# M_2_SoM_breakout_board_v0_5.net
KiCad netlist of a schematic drawn in EAGLE
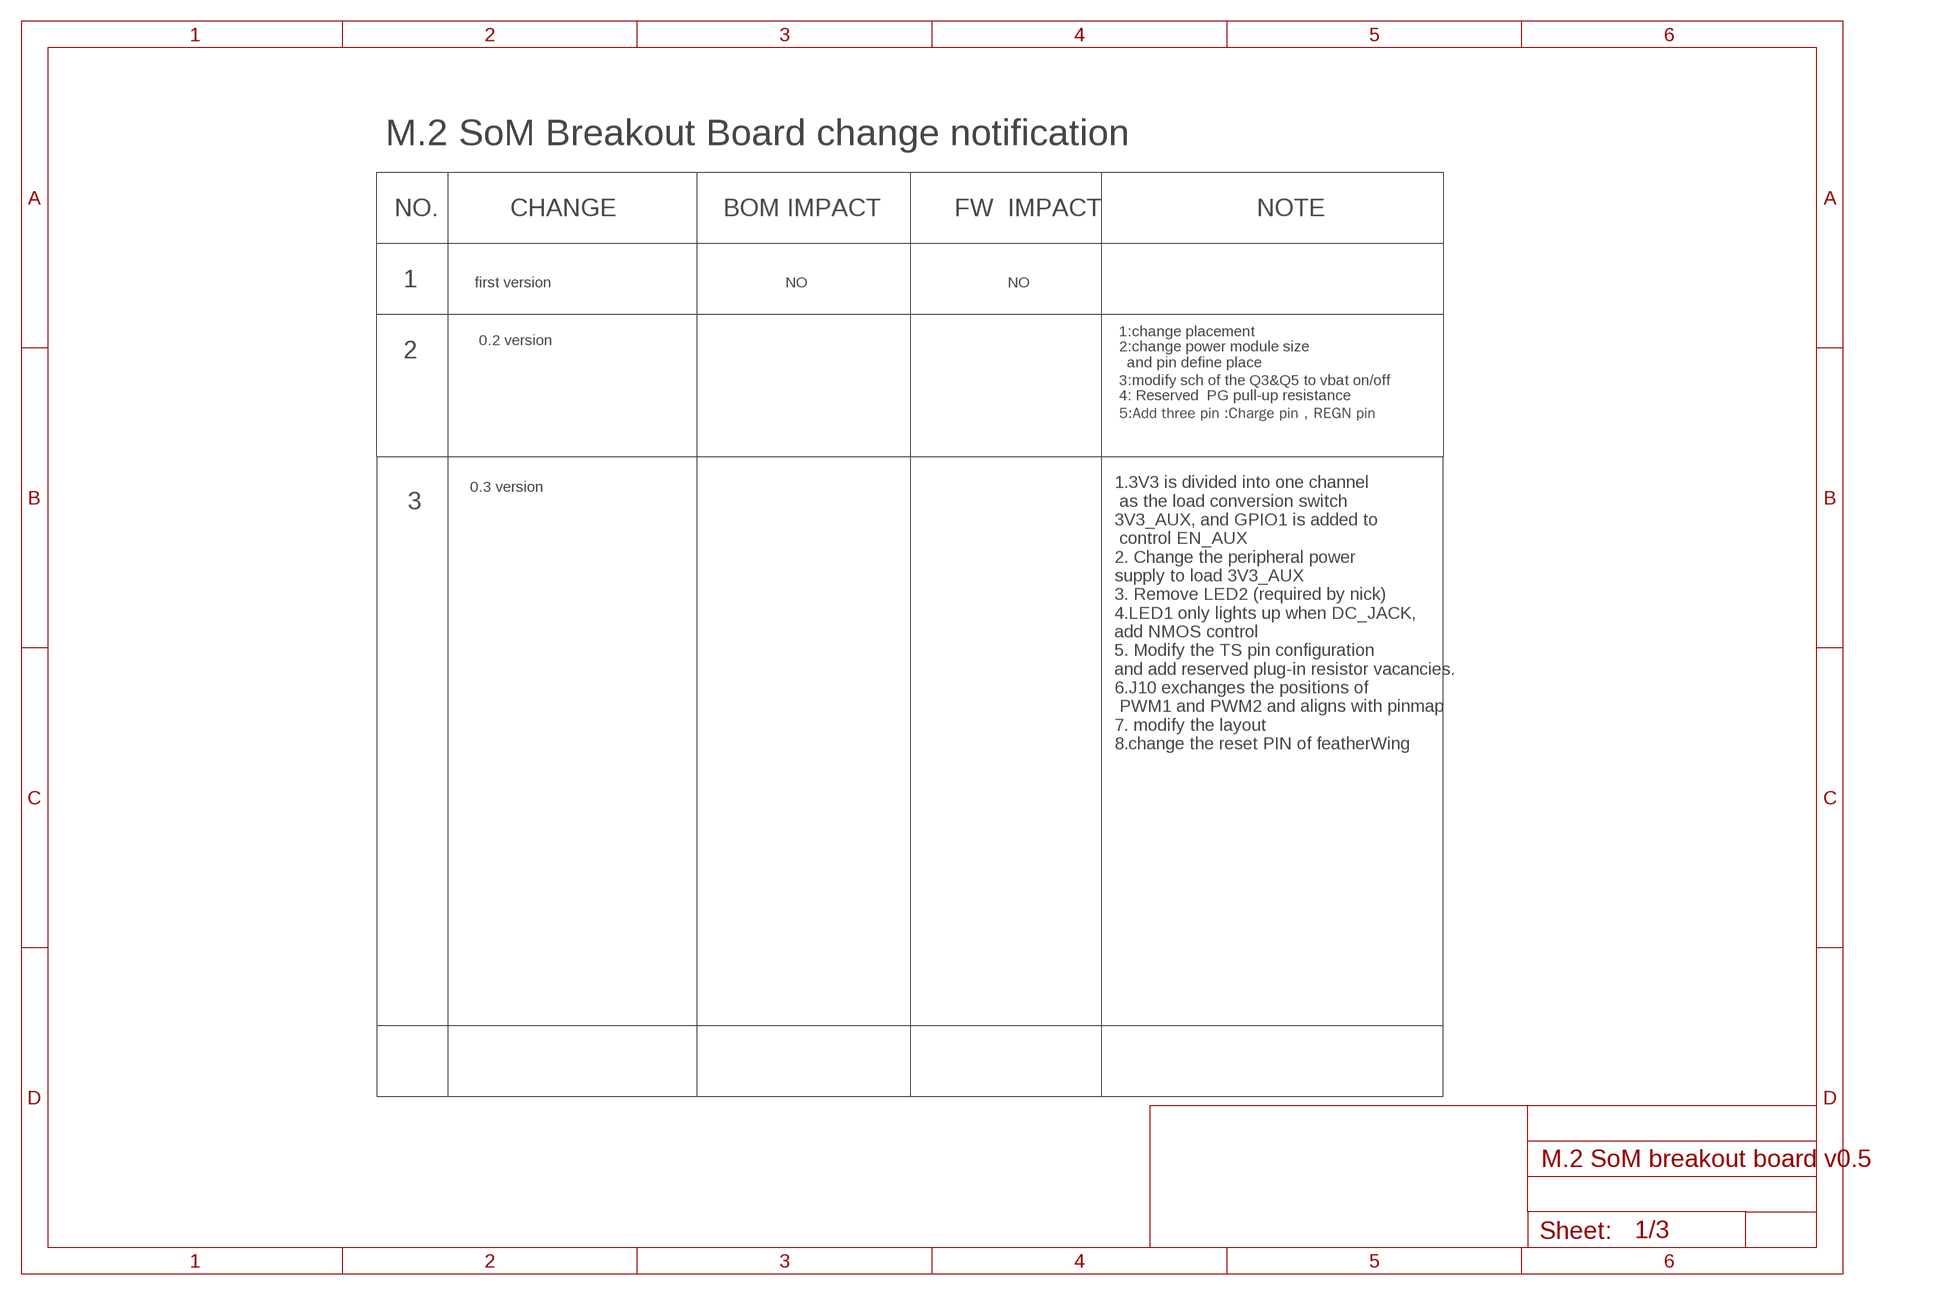
[diagram p0: schematic, sheet 1]
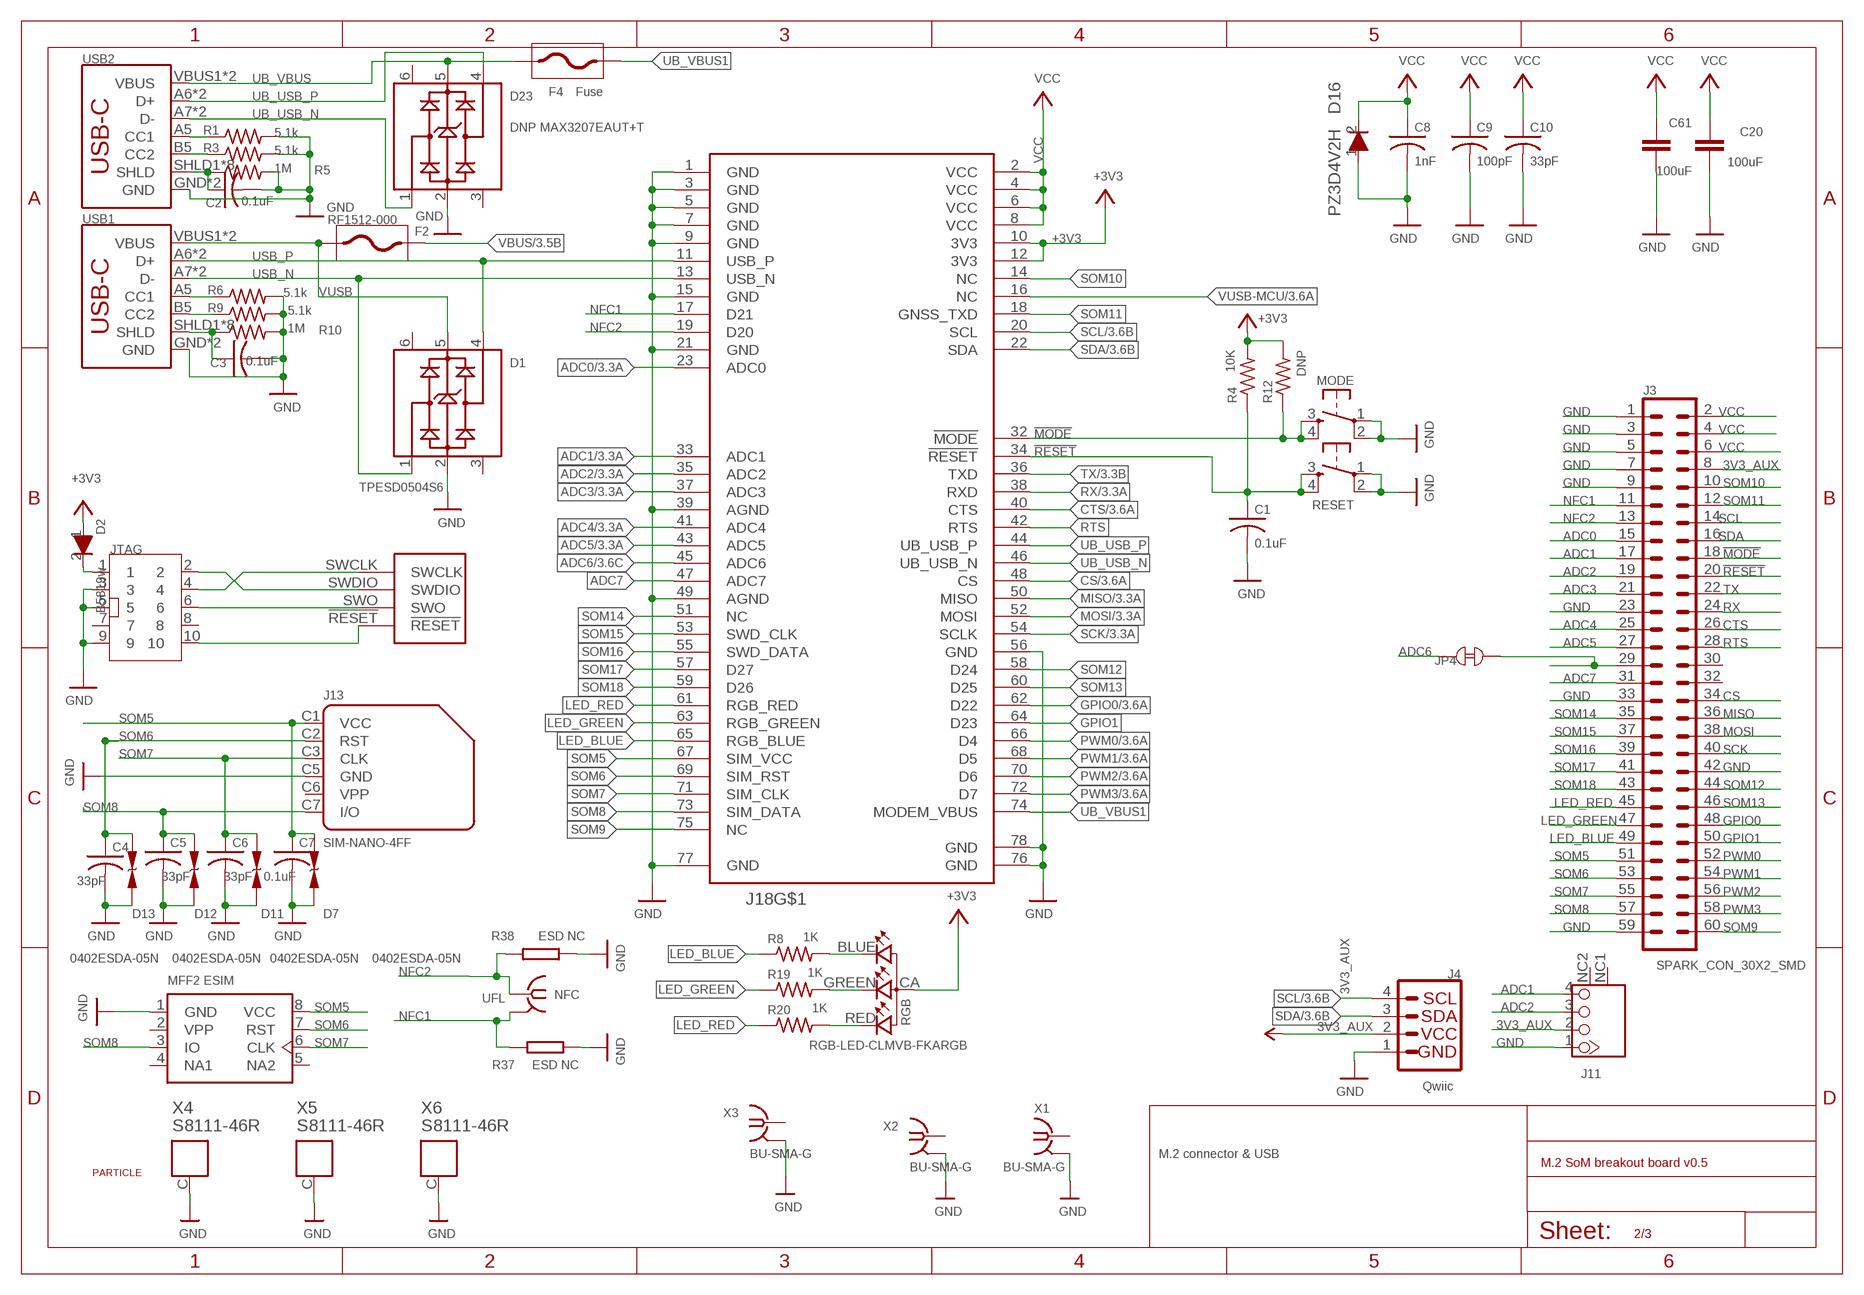
[diagram p1: schematic, sheet 2]
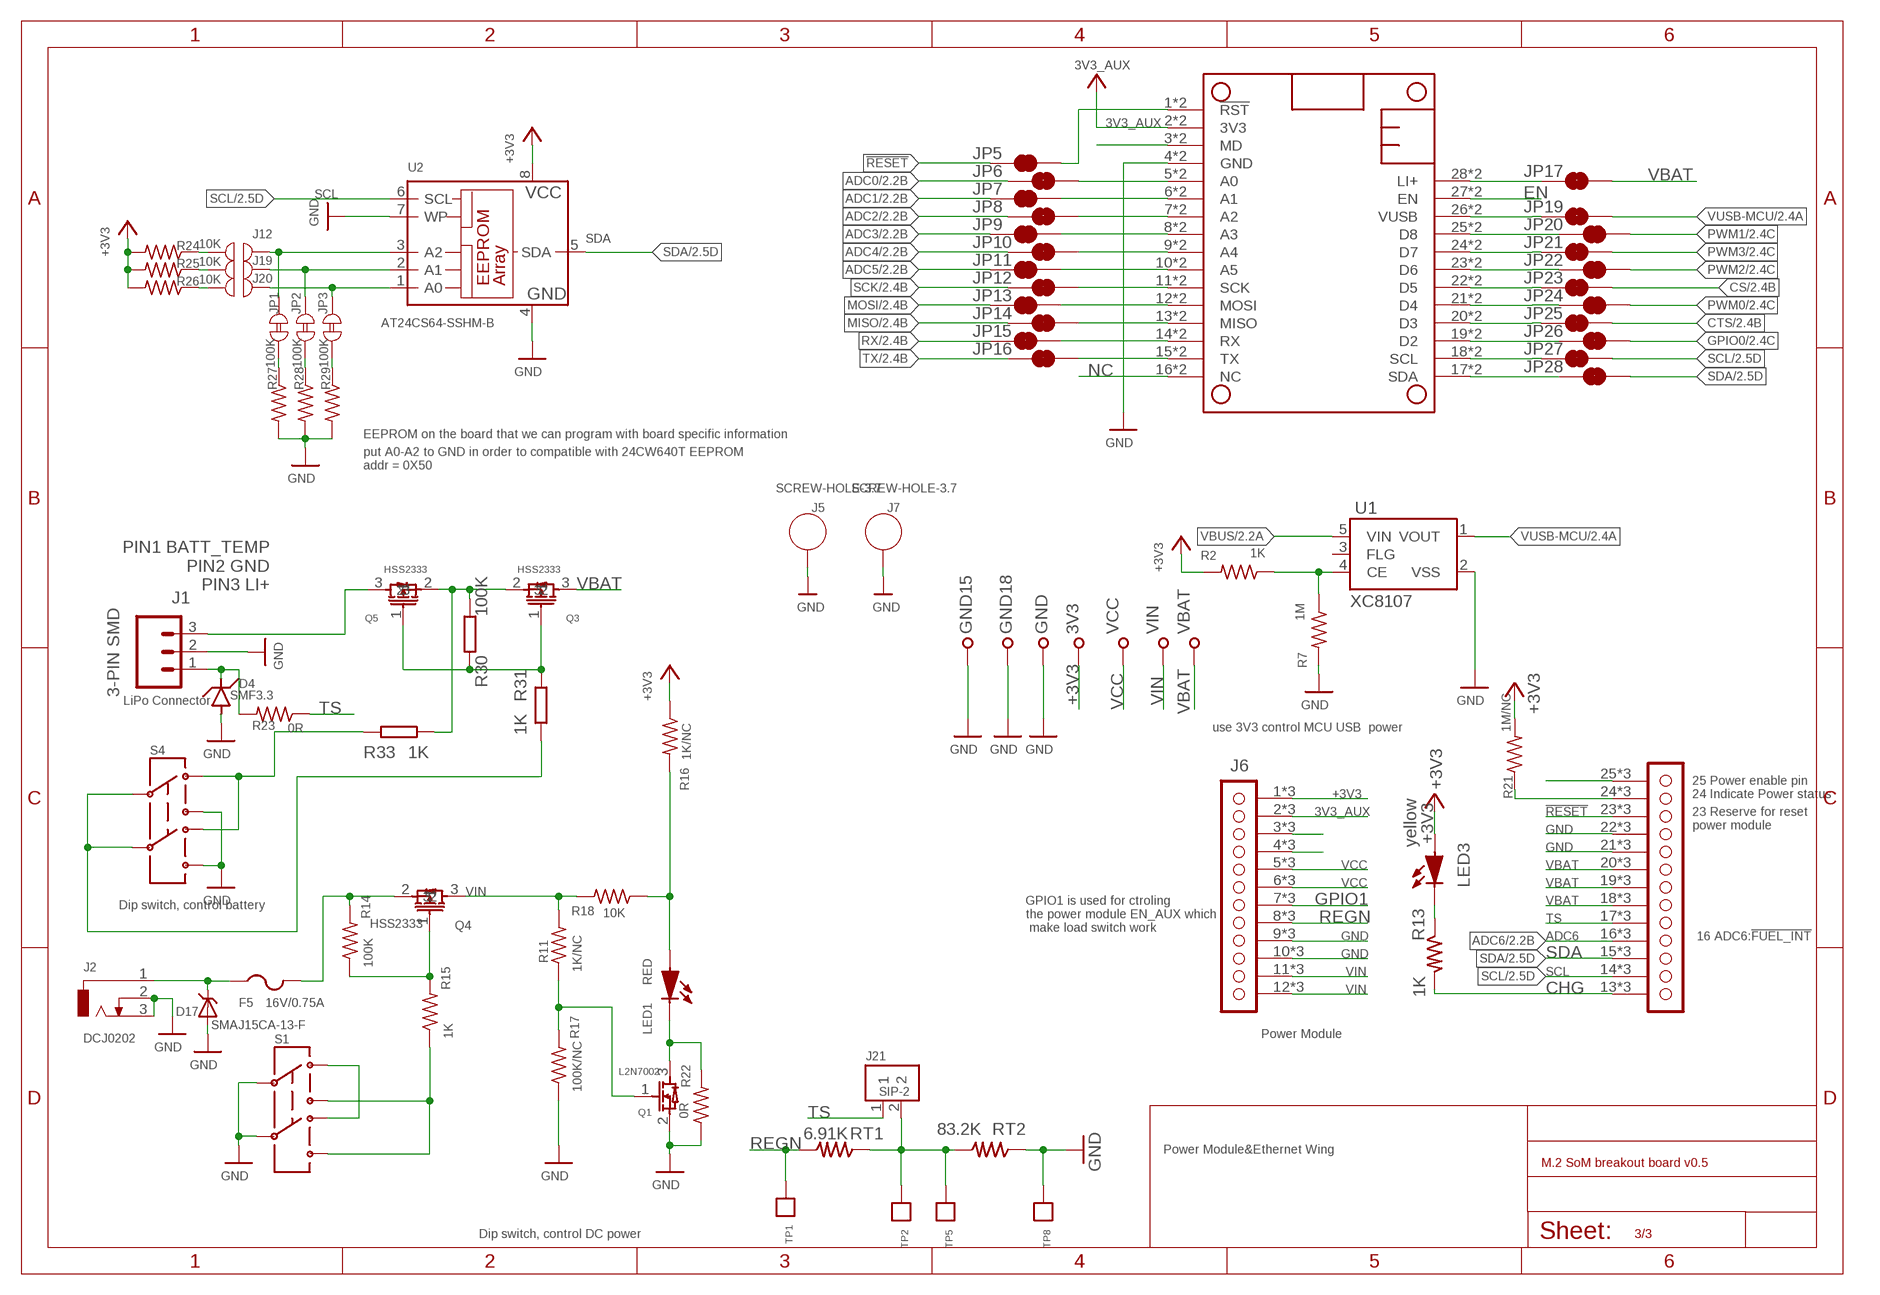
[diagram p2: schematic, sheet 3]

(export (version "E")
  (design (tool "Eeschema 10.0.6"))
  (components
    (comp (ref "3V3")
      (value "TP-S2751-46R")
      (footprint "eagle-import:S2751-46R")
      (libsource (lib "eagle-import") (part "TP-S2751-46R"))
    )
    (comp (ref "D4")
      (value "SMF3.3")
      (footprint "eagle-import:SOD-123FL")
      (libsource (lib "eagle-import") (part "TVS-DIODE-SOD123FL"))
    )
    (comp (ref "D17")
      (value "SMAJ15CA-13-F")
      (footprint "eagle-import:SMADIODE")
      (libsource (lib "eagle-import") (part "DIODE-ZENER"))
    )
    (comp (ref "F5")
      (value "16V/0.75A")
      (footprint "eagle-import:1812")
      (libsource (lib "eagle-import") (part "PTCFUSE-1812"))
    )
    (comp (ref "GND")
      (value "TP-S2751-46R")
      (footprint "eagle-import:S2751-46R")
      (libsource (lib "eagle-import") (part "TP-S2751-46R"))
    )
    (comp (ref "GND15")
      (value "TP-S2751-46R")
      (footprint "eagle-import:S2751-46R")
      (libsource (lib "eagle-import") (part "TP-S2751-46R"))
    )
    (comp (ref "GND18")
      (value "TP-S2751-46R")
      (footprint "eagle-import:S2751-46R")
      (libsource (lib "eagle-import") (part "TP-S2751-46R"))
    )
    (comp (ref "J1")
      (value "3-PIN SMD")
      (footprint "eagle-import:JST-3-SMD")
      (libsource (lib "eagle-import") (part "CONN_03JST-SMD"))
    )
    (comp (ref "J2")
      (value "DCJ0202")
      (footprint "eagle-import:DCJ0202")
      (libsource (lib "eagle-import") (part "DCJ0202"))
    )
    (comp (ref "J5")
      (value "SCREW-HOLE-3.7")
      (footprint "eagle-import:SCREW-HOLE-3.7")
      (libsource (lib "eagle-import") (part "SCREW-HOLE-3.7"))
    )
    (comp (ref "J6")
      (value "M.2-SOM-BREAKOUT-BOARD-V0.2-0228_PARTICLE-SZ_PARTICLE-POWER-MODULE")
      (footprint "eagle-import:M.2-SOM-BREAKOUT-BOARD-V0.2-0228_PARTICLE-SZ_PARTICLE-POWER-MODULE")
      (libsource (lib "eagle-import") (part "M.2-SOM-BREAKOUT-BOARD-V0.2-0228_PARTICLE-SZ_PARTICLE-POWER-MODULE"))
    )
    (comp (ref "J7")
      (value "SCREW-HOLE-3.7")
      (footprint "eagle-import:SCREW-HOLE-3.7")
      (libsource (lib "eagle-import") (part "SCREW-HOLE-3.7"))
    )
    (comp (ref "J12")
      (value "TP_OPEN")
      (footprint "eagle-import:TP_OPEN")
      (libsource (lib "eagle-import") (part "TP_OPEN"))
    )
    (comp (ref "J19")
      (value "TP_OPEN")
      (footprint "eagle-import:TP_OPEN")
      (libsource (lib "eagle-import") (part "TP_OPEN"))
    )
    (comp (ref "J20")
      (value "TP_OPEN")
      (footprint "eagle-import:TP_OPEN")
      (libsource (lib "eagle-import") (part "TP_OPEN"))
    )
    (comp (ref "J21")
      (value "SIP-2")
      (footprint "eagle-import:SIP-2")
      (libsource (lib "eagle-import") (part "SIP-2"))
    )
    (comp (ref "JP1")
      (value "TP_SHORT")
      (footprint "eagle-import:TP_SHORT")
      (libsource (lib "eagle-import") (part "TP_SHORT"))
    )
    (comp (ref "JP2")
      (value "TP_SHORT")
      (footprint "eagle-import:TP_SHORT")
      (libsource (lib "eagle-import") (part "TP_SHORT"))
    )
    (comp (ref "JP3")
      (value "TP_SHORT")
      (footprint "eagle-import:TP_SHORT")
      (libsource (lib "eagle-import") (part "TP_SHORT"))
    )
    (comp (ref "JP5")
      (value "JUMPER-SMT_2_NC_TRACE_NO-SILK")
      (footprint "eagle-import:SMT-JUMPER_2_NC_TRACE_NO-SILK")
      (libsource (lib "eagle-import") (part "JUMPER-SMT_2_NC_TRACE_NO-SILK"))
    )
    (comp (ref "JP6")
      (value "JUMPER-SMT_2_NC_TRACE_NO-SILK")
      (footprint "eagle-import:SMT-JUMPER_2_NC_TRACE_NO-SILK")
      (libsource (lib "eagle-import") (part "JUMPER-SMT_2_NC_TRACE_NO-SILK"))
    )
    (comp (ref "JP7")
      (value "JUMPER-SMT_2_NC_TRACE_NO-SILK")
      (footprint "eagle-import:SMT-JUMPER_2_NC_TRACE_NO-SILK")
      (libsource (lib "eagle-import") (part "JUMPER-SMT_2_NC_TRACE_NO-SILK"))
    )
    (comp (ref "JP8")
      (value "JUMPER-SMT_2_NC_TRACE_NO-SILK")
      (footprint "eagle-import:SMT-JUMPER_2_NC_TRACE_NO-SILK")
      (libsource (lib "eagle-import") (part "JUMPER-SMT_2_NC_TRACE_NO-SILK"))
    )
    (comp (ref "JP9")
      (value "JUMPER-SMT_2_NC_TRACE_NO-SILK")
      (footprint "eagle-import:SMT-JUMPER_2_NC_TRACE_NO-SILK")
      (libsource (lib "eagle-import") (part "JUMPER-SMT_2_NC_TRACE_NO-SILK"))
    )
    (comp (ref "JP10")
      (value "JUMPER-SMT_2_NC_TRACE_NO-SILK")
      (footprint "eagle-import:SMT-JUMPER_2_NC_TRACE_NO-SILK")
      (libsource (lib "eagle-import") (part "JUMPER-SMT_2_NC_TRACE_NO-SILK"))
    )
    (comp (ref "JP11")
      (value "JUMPER-SMT_2_NC_TRACE_NO-SILK")
      (footprint "eagle-import:SMT-JUMPER_2_NC_TRACE_NO-SILK")
      (libsource (lib "eagle-import") (part "JUMPER-SMT_2_NC_TRACE_NO-SILK"))
    )
    (comp (ref "JP12")
      (value "JUMPER-SMT_2_NC_TRACE_NO-SILK")
      (footprint "eagle-import:SMT-JUMPER_2_NC_TRACE_NO-SILK")
      (libsource (lib "eagle-import") (part "JUMPER-SMT_2_NC_TRACE_NO-SILK"))
    )
    (comp (ref "JP13")
      (value "JUMPER-SMT_2_NC_TRACE_NO-SILK")
      (footprint "eagle-import:SMT-JUMPER_2_NC_TRACE_NO-SILK")
      (libsource (lib "eagle-import") (part "JUMPER-SMT_2_NC_TRACE_NO-SILK"))
    )
    (comp (ref "JP14")
      (value "JUMPER-SMT_2_NC_TRACE_NO-SILK")
      (footprint "eagle-import:SMT-JUMPER_2_NC_TRACE_NO-SILK")
      (libsource (lib "eagle-import") (part "JUMPER-SMT_2_NC_TRACE_NO-SILK"))
    )
    (comp (ref "JP15")
      (value "JUMPER-SMT_2_NC_TRACE_NO-SILK")
      (footprint "eagle-import:SMT-JUMPER_2_NC_TRACE_NO-SILK")
      (libsource (lib "eagle-import") (part "JUMPER-SMT_2_NC_TRACE_NO-SILK"))
    )
    (comp (ref "JP16")
      (value "JUMPER-SMT_2_NC_TRACE_NO-SILK")
      (footprint "eagle-import:SMT-JUMPER_2_NC_TRACE_NO-SILK")
      (libsource (lib "eagle-import") (part "JUMPER-SMT_2_NC_TRACE_NO-SILK"))
    )
    (comp (ref "JP17")
      (value "JUMPER-SMT_2_NC_TRACE_NO-SILK")
      (footprint "eagle-import:SMT-JUMPER_2_NC_TRACE_NO-SILK")
      (libsource (lib "eagle-import") (part "JUMPER-SMT_2_NC_TRACE_NO-SILK"))
    )
    (comp (ref "JP19")
      (value "JUMPER-SMT_2_NC_TRACE_NO-SILK")
      (footprint "eagle-import:SMT-JUMPER_2_NC_TRACE_NO-SILK")
      (libsource (lib "eagle-import") (part "JUMPER-SMT_2_NC_TRACE_NO-SILK"))
    )
    (comp (ref "JP20")
      (value "JUMPER-SMT_2_NC_TRACE_NO-SILK")
      (footprint "eagle-import:SMT-JUMPER_2_NC_TRACE_NO-SILK")
      (libsource (lib "eagle-import") (part "JUMPER-SMT_2_NC_TRACE_NO-SILK"))
    )
    (comp (ref "JP21")
      (value "JUMPER-SMT_2_NC_TRACE_NO-SILK")
      (footprint "eagle-import:SMT-JUMPER_2_NC_TRACE_NO-SILK")
      (libsource (lib "eagle-import") (part "JUMPER-SMT_2_NC_TRACE_NO-SILK"))
    )
    (comp (ref "JP22")
      (value "JUMPER-SMT_2_NC_TRACE_NO-SILK")
      (footprint "eagle-import:SMT-JUMPER_2_NC_TRACE_NO-SILK")
      (libsource (lib "eagle-import") (part "JUMPER-SMT_2_NC_TRACE_NO-SILK"))
    )
    (comp (ref "JP23")
      (value "JUMPER-SMT_2_NC_TRACE_NO-SILK")
      (footprint "eagle-import:SMT-JUMPER_2_NC_TRACE_NO-SILK")
      (libsource (lib "eagle-import") (part "JUMPER-SMT_2_NC_TRACE_NO-SILK"))
    )
    (comp (ref "JP24")
      (value "JUMPER-SMT_2_NC_TRACE_NO-SILK")
      (footprint "eagle-import:SMT-JUMPER_2_NC_TRACE_NO-SILK")
      (libsource (lib "eagle-import") (part "JUMPER-SMT_2_NC_TRACE_NO-SILK"))
    )
    (comp (ref "JP25")
      (value "JUMPER-SMT_2_NC_TRACE_NO-SILK")
      (footprint "eagle-import:SMT-JUMPER_2_NC_TRACE_NO-SILK")
      (libsource (lib "eagle-import") (part "JUMPER-SMT_2_NC_TRACE_NO-SILK"))
    )
    (comp (ref "JP26")
      (value "JUMPER-SMT_2_NC_TRACE_NO-SILK")
      (footprint "eagle-import:SMT-JUMPER_2_NC_TRACE_NO-SILK")
      (libsource (lib "eagle-import") (part "JUMPER-SMT_2_NC_TRACE_NO-SILK"))
    )
    (comp (ref "JP27")
      (value "JUMPER-SMT_2_NC_TRACE_NO-SILK")
      (footprint "eagle-import:SMT-JUMPER_2_NC_TRACE_NO-SILK")
      (libsource (lib "eagle-import") (part "JUMPER-SMT_2_NC_TRACE_NO-SILK"))
    )
    (comp (ref "JP28")
      (value "JUMPER-SMT_2_NC_TRACE_NO-SILK")
      (footprint "eagle-import:SMT-JUMPER_2_NC_TRACE_NO-SILK")
      (libsource (lib "eagle-import") (part "JUMPER-SMT_2_NC_TRACE_NO-SILK"))
    )
    (comp (ref "LED1")
      (value "RED")
      (footprint "eagle-import:LED0603")
      (libsource (lib "eagle-import") (part "LED"))
    )
    (comp (ref "LED3")
      (value "yellow")
      (footprint "eagle-import:LED0603")
      (libsource (lib "eagle-import") (part "LED"))
    )
    (comp (ref "MS1")
      (value "PARTICLE_MESH_SMTDUAL")
      (footprint "eagle-import:FEATHERWING_SMT2")
      (libsource (lib "eagle-import") (part "PARTICLE_MESH_SMTDUAL"))
    )
    (comp (ref "Q1")
      (value "L2N7002")
      (footprint "eagle-import:SOT323")
      (libsource (lib "eagle-import") (part "NMOSSOT323"))
    )
    (comp (ref "Q3")
      (value "HSS2333")
      (footprint "eagle-import:SOT-23")
      (libsource (lib "eagle-import") (part "PMOS"))
    )
    (comp (ref "Q4")
      (value "HSS2333")
      (footprint "eagle-import:SOT-23")
      (libsource (lib "eagle-import") (part "PMOS"))
    )
    (comp (ref "Q5")
      (value "HSS2333")
      (footprint "eagle-import:SOT-23")
      (libsource (lib "eagle-import") (part "PMOS"))
    )
    (comp (ref "R2")
      (value "1K")
      (footprint "eagle-import:R0402_B")
      (libsource (lib "eagle-import") (part "R-US_"))
    )
    (comp (ref "R7")
      (value "1M")
      (footprint "eagle-import:R0402_B")
      (libsource (lib "eagle-import") (part "R-US_"))
    )
    (comp (ref "R11")
      (value "1K/NC")
      (footprint "eagle-import:R0402_B")
      (libsource (lib "eagle-import") (part "R-US_"))
    )
    (comp (ref "R13")
      (value "1K")
      (footprint "eagle-import:R-0402S")
      (libsource (lib "eagle-import") (part "particle SZ_RES0402S"))
    )
    (comp (ref "R14")
      (value "100K")
      (footprint "eagle-import:R0402_B")
      (libsource (lib "eagle-import") (part "R-US_"))
    )
    (comp (ref "R15")
      (value "1K")
      (footprint "eagle-import:R0402_B")
      (libsource (lib "eagle-import") (part "R-US_"))
    )
    (comp (ref "R16")
      (value "1K/NC")
      (footprint "eagle-import:R0402_B")
      (libsource (lib "eagle-import") (part "R-US_"))
    )
    (comp (ref "R17")
      (value "100K/NC")
      (footprint "eagle-import:R0402_B")
      (libsource (lib "eagle-import") (part "R-US_"))
    )
    (comp (ref "R18")
      (value "10K")
      (footprint "eagle-import:R0402_B")
      (libsource (lib "eagle-import") (part "R-US_"))
    )
    (comp (ref "R21")
      (value "1M/NC")
      (footprint "eagle-import:R0402_B")
      (libsource (lib "eagle-import") (part "R-US_"))
    )
    (comp (ref "R22")
      (value "0R")
      (footprint "eagle-import:R0402_B")
      (libsource (lib "eagle-import") (part "R-US_"))
    )
    (comp (ref "R23")
      (value "0R")
      (footprint "eagle-import:R0402_B")
      (libsource (lib "eagle-import") (part "R-US_"))
    )
    (comp (ref "R24")
      (value "10K")
      (footprint "eagle-import:R0402_B")
      (libsource (lib "eagle-import") (part "R-US_"))
    )
    (comp (ref "R25")
      (value "10K")
      (footprint "eagle-import:R0402_B")
      (libsource (lib "eagle-import") (part "R-US_"))
    )
    (comp (ref "R26")
      (value "10K")
      (footprint "eagle-import:R0402_B")
      (libsource (lib "eagle-import") (part "R-US_"))
    )
    (comp (ref "R27")
      (value "100K")
      (footprint "eagle-import:R0402_B")
      (libsource (lib "eagle-import") (part "R-US_"))
    )
    (comp (ref "R28")
      (value "100K")
      (footprint "eagle-import:R0402_B")
      (libsource (lib "eagle-import") (part "R-US_"))
    )
    (comp (ref "R29")
      (value "100K")
      (footprint "eagle-import:R0402_B")
      (libsource (lib "eagle-import") (part "R-US_"))
    )
    (comp (ref "R30")
      (value "100K")
      (footprint "eagle-import:R0603")
      (libsource (lib "eagle-import") (part "RESR0603"))
    )
    (comp (ref "R31")
      (value "1K")
      (footprint "eagle-import:R-0402S")
      (libsource (lib "eagle-import") (part "RES0402S"))
    )
    (comp (ref "R33")
      (value "1K")
      (footprint "eagle-import:R-0402S")
      (libsource (lib "eagle-import") (part "RES0402S"))
    )
    (comp (ref "RT1")
      (value "6.91K")
      (footprint "eagle-import:R-0603A")
      (libsource (lib "eagle-import") (part "RESR0603A"))
    )
    (comp (ref "RT2")
      (value "83.2K")
      (footprint "eagle-import:R-0603A")
      (libsource (lib "eagle-import") (part "RESR0603A"))
    )
    (comp (ref "S1")
      (value "SWITCH-DPDT")
      (footprint "eagle-import:SWITCH-2.5X3.2-6")
      (libsource (lib "eagle-import") (part "SWITCH-DPDT"))
    )
    (comp (ref "S4")
      (value "SWITCH-DPDT")
      (footprint "eagle-import:SWITCH-2.5X3.2-6")
      (libsource (lib "eagle-import") (part "SWITCH-DPDT"))
    )
    (comp (ref "TP1")
      (value "TPTPEB")
      (footprint "eagle-import:TPEB")
      (libsource (lib "eagle-import") (part "TPTPEB"))
    )
    (comp (ref "TP2")
      (value "TPTPEB")
      (footprint "eagle-import:TPEB")
      (libsource (lib "eagle-import") (part "TPTPEB"))
    )
    (comp (ref "TP5")
      (value "TPTPEB")
      (footprint "eagle-import:TPEB")
      (libsource (lib "eagle-import") (part "TPTPEB"))
    )
    (comp (ref "TP8")
      (value "TPTPEB")
      (footprint "eagle-import:TPEB")
      (libsource (lib "eagle-import") (part "TPTPEB"))
    )
    (comp (ref "U1")
      (value "XC8107")
      (footprint "eagle-import:SOT25")
      (libsource (lib "eagle-import") (part "XC8107SOT25"))
    )
    (comp (ref "U2")
      (value "AT24CS64-SSHM-B")
      (footprint "eagle-import:SO-08")
      (fields (field (name "MF") "MICROCHIP") (field (name "MPN") "24AA01/SN"))
      (libsource (lib "eagle-import") (part "24SNAA01"))
    )
    (comp (ref "VBAT")
      (value "TP-S2751-46R")
      (footprint "eagle-import:S2751-46R")
      (libsource (lib "eagle-import") (part "TP-S2751-46R"))
    )
    (comp (ref "VCC")
      (value "TP-S2751-46R")
      (footprint "eagle-import:S2751-46R")
      (libsource (lib "eagle-import") (part "TP-S2751-46R"))
    )
    (comp (ref "VIN")
      (value "TP-S2751-46R")
      (footprint "eagle-import:S2751-46R")
      (libsource (lib "eagle-import") (part "TP-S2751-46R"))
    )
    (comp (ref "C1")
      (value "0.1uF")
      (footprint "eagle-import:C0402_B")
      (libsource (lib "eagle-import") (part "C-US"))
    )
    (comp (ref "C2")
      (value "0.1uF")
      (footprint "eagle-import:C0402_B")
      (libsource (lib "eagle-import") (part "C-US"))
    )
    (comp (ref "C3")
      (value "0.1uF")
      (footprint "eagle-import:C0402_B")
      (libsource (lib "eagle-import") (part "C-US"))
    )
    (comp (ref "C4")
      (value "33pF")
      (footprint "eagle-import:C0402_B")
      (libsource (lib "eagle-import") (part "C-US"))
    )
    (comp (ref "C5")
      (value "33pF")
      (footprint "eagle-import:C0402_B")
      (libsource (lib "eagle-import") (part "C-US"))
    )
    (comp (ref "C6")
      (value "33pF")
      (footprint "eagle-import:C0402_B")
      (libsource (lib "eagle-import") (part "C-US"))
    )
    (comp (ref "C7")
      (value "0.1uF")
      (footprint "eagle-import:C0402_B")
      (libsource (lib "eagle-import") (part "C-US"))
    )
    (comp (ref "C8")
      (value "1nF")
      (footprint "eagle-import:C0402_B")
      (libsource (lib "eagle-import") (part "C-US"))
    )
    (comp (ref "C9")
      (value "100pF")
      (footprint "eagle-import:C0402_B")
      (libsource (lib "eagle-import") (part "C-US"))
    )
    (comp (ref "C10")
      (value "33pF")
      (footprint "eagle-import:C0402_B")
      (libsource (lib "eagle-import") (part "C-US"))
    )
    (comp (ref "C20")
      (value "100uF")
      (footprint "eagle-import:C1206K")
      (libsource (lib "eagle-import") (part "C-EUC1206K"))
    )
    (comp (ref "C61")
      (value "100uF")
      (footprint "eagle-import:C1206K")
      (libsource (lib "eagle-import") (part "C-EUC1206K"))
    )
    (comp (ref "D1")
      (value "TPESD0504S6")
      (footprint "eagle-import:SOT23-6")
      (fields (field (name "MFG") "MAXIM") (field (name "MPN") "MAX3207EAUT+T"))
      (libsource (lib "eagle-import") (part "MAX3207EAUT+T"))
    )
    (comp (ref "D2")
      (value "B5819w")
      (footprint "eagle-import:SOD-123")
      (libsource (lib "eagle-import") (part "DIODESOD123"))
    )
    (comp (ref "D7")
      (value "0402ESDA-05N")
      (footprint "eagle-import:C0402")
      (libsource (lib "eagle-import") (part "ESD"))
    )
    (comp (ref "D11")
      (value "0402ESDA-05N")
      (footprint "eagle-import:C0402")
      (libsource (lib "eagle-import") (part "ESD"))
    )
    (comp (ref "D12")
      (value "0402ESDA-05N")
      (footprint "eagle-import:C0402")
      (libsource (lib "eagle-import") (part "ESD"))
    )
    (comp (ref "D13")
      (value "0402ESDA-05N")
      (footprint "eagle-import:C0402")
      (libsource (lib "eagle-import") (part "ESD"))
    )
    (comp (ref "D16")
      (value "PZ3D4V2H")
      (footprint "eagle-import:SOD-323")
      (libsource (lib "eagle-import") (part "DIODESOD323"))
    )
    (comp (ref "D23")
      (value "DNP MAX3207EAUT+T")
      (footprint "eagle-import:SOT23-6")
      (fields (field (name "MFG") "MAXIM") (field (name "MPN") "MAX3207EAUT+T"))
      (libsource (lib "eagle-import") (part "MAX3207EAUT+T"))
    )
    (comp (ref "F2")
      (value "RF1512-000")
      (footprint "eagle-import:F0805")
      (libsource (lib "eagle-import") (part "FUSE"))
    )
    (comp (ref "F4")
      (value "Fuse")
      (footprint "eagle-import:F0805")
      (libsource (lib "eagle-import") (part "FUSE"))
    )
    (comp (ref "J3")
      (value "SPARK_CON_30X2_SMD")
      (footprint "eagle-import:SPARK_CON_30X2_SMD")
      (libsource (lib "eagle-import") (part "SPARK_CON_30X2_SMD"))
    )
    (comp (ref "J4")
      (value "QWIIC_CONNECTORJS-1MM")
      (footprint "eagle-import:1X04_1MM_RA")
      (libsource (lib "eagle-import") (part "QWIIC_CONNECTORJS-1MM"))
    )
    (comp (ref "J11")
      (value "WAFER-HY2.0-4PWB")
      (footprint "eagle-import:M.2-SOM-BREAKOUT-BOARD-V0.2-0228_WAFER-HY2.0-4PWB")
      (libsource (lib "eagle-import") (part "M.2-SOM-BREAKOUT-BOARD-V0.2-0228_WAFER-HY2.0-4PWB"))
    )
    (comp (ref "J13")
      (value "SIM-NANO-4FF")
      (footprint "eagle-import:GCT-SIM8100")
      (libsource (lib "eagle-import") (part "SIM-NANO-4FF"))
    )
    (comp (ref "J18")
      (value "PARTICLE-STUDIOS_M_SERIES_M.2KEY")
      (footprint "eagle-import:PARTICLE-STUDIOS_PARTICLE_M.2EKEY_3.65MM_DRILL")
      (libsource (lib "eagle-import") (part "PARTICLE-STUDIOS_M_SERIES_M.2KEY"))
    )
    (comp (ref "JP4")
      (value "TP_SHORT")
      (footprint "eagle-import:TP_SHORT")
      (libsource (lib "eagle-import") (part "TP_SHORT"))
    )
    (comp (ref "JTAG")
      (value "CONN5X2")
      (footprint "eagle-import:CONN5X2_1.27")
      (fields (field (name "MFG") "KAWEEI") (field (name "MPN") "P6014A-M2GC-030-10"))
      (libsource (lib "eagle-import") (part "CONN5X2"))
    )
    (comp (ref "MODE")
      (value "TAC_SWITCHSMD")
      (footprint "eagle-import:TACTILE_SWITCH_SMD")
      (fields (field (name "MFG") "HAOYU") (field (name "MPN") "TS-1185A-025C"))
      (libsource (lib "eagle-import") (part "TAC_SWITCHSMD"))
    )
    (comp (ref "NFC")
      (value "UFL")
      (footprint "eagle-import:IPEX-20279-001E")
      (libsource (lib "eagle-import") (part "IPEX-20279-001E"))
    )
    (comp (ref "R1")
      (value "5.1k")
      (footprint "eagle-import:R0402_B")
      (libsource (lib "eagle-import") (part "R-US_"))
    )
    (comp (ref "R3")
      (value "5.1k")
      (footprint "eagle-import:R0402_B")
      (libsource (lib "eagle-import") (part "R-US_"))
    )
    (comp (ref "R4")
      (value "10K")
      (footprint "eagle-import:R0402_B")
      (libsource (lib "eagle-import") (part "R-US_"))
    )
    (comp (ref "R5")
      (value "1M")
      (footprint "eagle-import:R0402_B")
      (libsource (lib "eagle-import") (part "R-US_"))
    )
    (comp (ref "R6")
      (value "5.1k")
      (footprint "eagle-import:R0402_B")
      (libsource (lib "eagle-import") (part "R-US_"))
    )
    (comp (ref "R8")
      (value "1K")
      (footprint "eagle-import:R0402_B")
      (libsource (lib "eagle-import") (part "R-US_"))
    )
    (comp (ref "R9")
      (value "5.1k")
      (footprint "eagle-import:R0402_B")
      (libsource (lib "eagle-import") (part "R-US_"))
    )
    (comp (ref "R10")
      (value "1M")
      (footprint "eagle-import:R0402_B")
      (libsource (lib "eagle-import") (part "R-US_"))
    )
    (comp (ref "R12")
      (value "DNP")
      (footprint "eagle-import:R0402_B")
      (libsource (lib "eagle-import") (part "R-US_"))
    )
    (comp (ref "R19")
      (value "1K")
      (footprint "eagle-import:R0402_B")
      (libsource (lib "eagle-import") (part "R-US_"))
    )
    (comp (ref "R20")
      (value "1K")
      (footprint "eagle-import:R0402_B")
      (libsource (lib "eagle-import") (part "R-US_"))
    )
    (comp (ref "R37")
      (value "ESD NC")
      (footprint "eagle-import:R-0402S")
      (libsource (lib "eagle-import") (part "RES0402S"))
    )
    (comp (ref "R38")
      (value "ESD NC")
      (footprint "eagle-import:R-0402S")
      (libsource (lib "eagle-import") (part "RES0402S"))
    )
    (comp (ref "RESET")
      (value "TAC_SWITCHSMD")
      (footprint "eagle-import:TACTILE_SWITCH_SMD")
      (fields (field (name "MFG") "HAOYU") (field (name "MPN") "TS-1185A-025C"))
      (libsource (lib "eagle-import") (part "TAC_SWITCHSMD"))
    )
    (comp (ref "RGB")
      (value "RGB-LED-CLMVB-FKARGB")
      (footprint "eagle-import:PLCC4-2MM-RGB")
      (libsource (lib "eagle-import") (part "RGB-LED-CLMVB-FKARGB"))
    )
    (comp (ref "U$6")
      (value "PARTICLE-LOGO")
      (footprint "eagle-import:PARTICLE-LOGO")
      (libsource (lib "eagle-import") (part "PARTICLE-LOGO"))
    )
    (comp (ref "U7")
      (value "NC")
      (footprint "eagle-import:MFF2")
      (libsource (lib "eagle-import") (part "ESIMSON8"))
    )
    (comp (ref "USB1")
      (value "USB_C16PIN")
      (footprint "eagle-import:USB-C-16P")
      (libsource (lib "eagle-import") (part "USB_C16PIN"))
    )
    (comp (ref "USB2")
      (value "USB_C16PIN")
      (footprint "eagle-import:USB-C-16P")
      (libsource (lib "eagle-import") (part "USB_C16PIN"))
    )
    (comp (ref "X1")
      (value "BU-SMA-G")
      (footprint "eagle-import:BU-SMA-G")
      (libsource (lib "eagle-import") (part "BU-SMA-G"))
    )
    (comp (ref "X2")
      (value "BU-SMA-G")
      (footprint "eagle-import:BU-SMA-G")
      (libsource (lib "eagle-import") (part "BU-SMA-G"))
    )
    (comp (ref "X3")
      (value "BU-SMA-G")
      (footprint "eagle-import:BU-SMA-G")
      (libsource (lib "eagle-import") (part "BU-SMA-G"))
    )
    (comp (ref "X4")
      (value "S8111-46R")
      (footprint "eagle-import:S8111-46R")
      (libsource (lib "eagle-import") (part "S8111-46R"))
    )
    (comp (ref "X5")
      (value "S8111-46R")
      (footprint "eagle-import:S8111-46R")
      (libsource (lib "eagle-import") (part "S8111-46R"))
    )
    (comp (ref "X6")
      (value "S8111-46R")
      (footprint "eagle-import:S8111-46R")
      (libsource (lib "eagle-import") (part "S8111-46R"))
    )
  )
  (nets
    (net (code "1") (name "+3V3") (class "Default")
      (node (ref "3V3") (pin "1") (pinfunction "TP_1") (pintype "bidirectional"))
      (node (ref "D2") (pin "1") (pinfunction "P$1_1") (pintype "bidirectional"))
      (node (ref "J18") (pin "10") (pinfunction "3V3_10") (pintype "power_in"))
      (node (ref "J18") (pin "12") (pinfunction "3V3_12") (pintype "power_in"))
      (node (ref "J6") (pin "1") (pinfunction "3V3_1") (pintype "passive"))
      (node (ref "J6") (pin "@1") (pinfunction "3V3_@1") (pintype "passive"))
      (node (ref "J6") (pin "P$1") (pinfunction "3V3_P$1") (pintype "passive"))
      (node (ref "LED3") (pin "1") (pinfunction "A_1") (pintype "bidirectional"))
      (node (ref "R12") (pin "2") (pinfunction "2_2") (pintype "passive"))
      (node (ref "R16") (pin "1") (pinfunction "1_1") (pintype "passive"))
      (node (ref "R2") (pin "2") (pinfunction "2_2") (pintype "passive"))
      (node (ref "R21") (pin "2") (pinfunction "2_2") (pintype "passive"))
      (node (ref "R24") (pin "2") (pinfunction "2_2") (pintype "passive"))
      (node (ref "R25") (pin "2") (pinfunction "2_2") (pintype "passive"))
      (node (ref "R26") (pin "2") (pinfunction "2_2") (pintype "passive"))
      (node (ref "R4") (pin "2") (pinfunction "2_2") (pintype "passive"))
      (node (ref "RGB") (pin "CA") (pinfunction "1_CA") (pintype "passive"))
      (node (ref "U2") (pin "8") (pinfunction "VCC_8") (pintype "power_in"))
    )
    (net (code "2") (name "3V3_AUX") (class "Default")
      (node (ref "J11") (pin "2") (pinfunction "2_2") (pintype "bidirectional"))
      (node (ref "J3") (pin "8") (pinfunction "8_8") (pintype "passive"))
      (node (ref "J4") (pin "2") (pinfunction "2_2") (pintype "power_in"))
      (node (ref "J6") (pin "2") (pinfunction "3V3_2") (pintype "passive"))
      (node (ref "J6") (pin "@2") (pinfunction "3V3_@2") (pintype "passive"))
      (node (ref "J6") (pin "P$2") (pinfunction "3V3_P$2") (pintype "passive"))
      (node (ref "MS1") (pin "2") (pinfunction "3V3_2") (pintype "power_in"))
      (node (ref "MS1") (pin "2'") (pinfunction "3V3_2'") (pintype "power_in"))
    )
    (net (code "3") (name "ADC0") (class "Default")
      (node (ref "J18") (pin "23") (pinfunction "ADC0_23") (pintype "bidirectional"))
      (node (ref "J3") (pin "15") (pinfunction "15_15") (pintype "passive"))
      (node (ref "JP6") (pin "1") (pinfunction "1_1") (pintype "passive"))
    )
    (net (code "4") (name "ADC1") (class "Default")
      (node (ref "J11") (pin "4") (pinfunction "4_4") (pintype "bidirectional"))
      (node (ref "J18") (pin "33") (pinfunction "ADC1_33") (pintype "bidirectional"))
      (node (ref "J3") (pin "17") (pinfunction "17_17") (pintype "passive"))
      (node (ref "JP7") (pin "1") (pinfunction "1_1") (pintype "passive"))
    )
    (net (code "5") (name "ADC2") (class "Default")
      (node (ref "J11") (pin "3") (pinfunction "3_3") (pintype "bidirectional"))
      (node (ref "J18") (pin "35") (pinfunction "ADC2_35") (pintype "bidirectional"))
      (node (ref "J3") (pin "19") (pinfunction "19_19") (pintype "passive"))
      (node (ref "JP8") (pin "1") (pinfunction "1_1") (pintype "passive"))
    )
    (net (code "6") (name "ADC3") (class "Default")
      (node (ref "J18") (pin "37") (pinfunction "ADC3_37") (pintype "bidirectional"))
      (node (ref "J3") (pin "21") (pinfunction "21_21") (pintype "passive"))
      (node (ref "JP9") (pin "1") (pinfunction "1_1") (pintype "passive"))
    )
    (net (code "7") (name "ADC4") (class "Default")
      (node (ref "J18") (pin "41") (pinfunction "ADC4_41") (pintype "bidirectional"))
      (node (ref "J3") (pin "25") (pinfunction "25_25") (pintype "passive"))
      (node (ref "JP10") (pin "1") (pinfunction "1_1") (pintype "passive"))
    )
    (net (code "8") (name "ADC5") (class "Default")
      (node (ref "J18") (pin "43") (pinfunction "ADC5_43") (pintype "bidirectional"))
      (node (ref "J3") (pin "27") (pinfunction "27_27") (pintype "passive"))
      (node (ref "JP11") (pin "1") (pinfunction "1_1") (pintype "passive"))
    )
    (net (code "9") (name "ADC6") (class "Default")
      (node (ref "J18") (pin "45") (pinfunction "ADC6_45") (pintype "bidirectional"))
      (node (ref "J6") (pin "16") (pinfunction "~{FUEL-INT}_16") (pintype "passive"))
      (node (ref "J6") (pin "@16") (pinfunction "~{FUEL-INT}_@16") (pintype "passive"))
      (node (ref "J6") (pin "P$16") (pinfunction "~{FUEL-INT}_P$16") (pintype "passive"))
      (node (ref "JP4") (pin "2") (pinfunction "2_2") (pintype "bidirectional"))
    )
    (net (code "10") (name "ADC7") (class "Default")
      (node (ref "J18") (pin "47") (pinfunction "ADC7_47") (pintype "bidirectional"))
      (node (ref "J3") (pin "31") (pinfunction "31_31") (pintype "passive"))
    )
    (net (code "11") (name "CHG") (class "Default")
      (node (ref "J6") (pin "13") (pinfunction "CHG_13") (pintype "passive"))
      (node (ref "J6") (pin "@13") (pinfunction "CHG_@13") (pintype "passive"))
      (node (ref "J6") (pin "P$13") (pinfunction "CHG_P$13") (pintype "passive"))
      (node (ref "R13") (pin "2") (pinfunction "2_2") (pintype "bidirectional"))
    )
    (net (code "12") (name "CS") (class "Default")
      (node (ref "J18") (pin "48") (pinfunction "CS_48") (pintype "bidirectional"))
      (node (ref "J3") (pin "34") (pinfunction "34_34") (pintype "passive"))
      (node (ref "JP23") (pin "2") (pinfunction "2_2") (pintype "passive"))
    )
    (net (code "13") (name "CTS") (class "Default")
      (node (ref "J18") (pin "40") (pinfunction "CTS_40") (pintype "bidirectional"))
      (node (ref "J3") (pin "26") (pinfunction "26_26") (pintype "passive"))
      (node (ref "JP25") (pin "2") (pinfunction "2_2") (pintype "passive"))
    )
    (net (code "14") (name "EN") (class "Default")
      (node (ref "MS1") (pin "27") (pinfunction "EN_27") (pintype "passive"))
      (node (ref "MS1") (pin "27'") (pinfunction "EN_27'") (pintype "passive"))
    )
    (net (code "15") (name "GND") (class "Default")
      (node (ref "C1") (pin "2") (pinfunction "2_2") (pintype "passive"))
      (node (ref "C10") (pin "2") (pinfunction "2_2") (pintype "passive"))
      (node (ref "C2") (pin "2") (pinfunction "2_2") (pintype "passive"))
      (node (ref "C20") (pin "2") (pinfunction "2_2") (pintype "passive"))
      (node (ref "C3") (pin "2") (pinfunction "2_2") (pintype "passive"))
      (node (ref "C4") (pin "2") (pinfunction "2_2") (pintype "passive"))
      (node (ref "C5") (pin "2") (pinfunction "2_2") (pintype "passive"))
      (node (ref "C6") (pin "2") (pinfunction "2_2") (pintype "passive"))
      (node (ref "C61") (pin "2") (pinfunction "2_2") (pintype "passive"))
      (node (ref "C7") (pin "2") (pinfunction "2_2") (pintype "passive"))
      (node (ref "C8") (pin "2") (pinfunction "2_2") (pintype "passive"))
      (node (ref "C9") (pin "2") (pinfunction "2_2") (pintype "passive"))
      (node (ref "D1") (pin "2") (pinfunction "2_2") (pintype "bidirectional"))
      (node (ref "D11") (pin "1") (pinfunction "1_1") (pintype "bidirectional"))
      (node (ref "D12") (pin "1") (pinfunction "1_1") (pintype "bidirectional"))
      (node (ref "D13") (pin "1") (pinfunction "1_1") (pintype "bidirectional"))
      (node (ref "D16") (pin "1") (pinfunction "P$1_1") (pintype "bidirectional"))
      (node (ref "D17") (pin "A") (pinfunction "A_A") (pintype "passive"))
      (node (ref "D23") (pin "2") (pinfunction "2_2") (pintype "bidirectional"))
      (node (ref "D4") (pin "A") (pinfunction "A_A") (pintype "passive"))
      (node (ref "D7") (pin "1") (pinfunction "1_1") (pintype "bidirectional"))
      (node (ref "GND") (pin "1") (pinfunction "TP_1") (pintype "bidirectional"))
      (node (ref "GND15") (pin "1") (pinfunction "TP_1") (pintype "bidirectional"))
      (node (ref "GND18") (pin "1") (pinfunction "TP_1") (pintype "bidirectional"))
      (node (ref "J1") (pin "2") (pinfunction "2_2") (pintype "passive"))
      (node (ref "J11") (pin "1") (pinfunction "1_1") (pintype "bidirectional"))
      (node (ref "J13") (pin "C5") (pinfunction "GND_C5") (pintype "passive"))
      (node (ref "J18") (pin "1") (pinfunction "GND_1") (pintype "power_in"))
      (node (ref "J18") (pin "15") (pinfunction "GND_15") (pintype "power_in"))
      (node (ref "J18") (pin "21") (pinfunction "GND_21") (pintype "power_in"))
      (node (ref "J18") (pin "3") (pinfunction "GND_3") (pintype "power_in"))
      (node (ref "J18") (pin "39") (pinfunction "AGND_39") (pintype "power_in"))
      (node (ref "J18") (pin "49") (pinfunction "AGND_49") (pintype "power_in"))
      (node (ref "J18") (pin "5") (pinfunction "GND_5") (pintype "power_in"))
      (node (ref "J18") (pin "56") (pinfunction "GND_56") (pintype "power_in"))
      (node (ref "J18") (pin "7") (pinfunction "GND_7") (pintype "power_in"))
      (node (ref "J18") (pin "76") (pinfunction "GND_76") (pintype "power_in"))
      (node (ref "J18") (pin "77") (pinfunction "GND_77") (pintype "power_in"))
      (node (ref "J18") (pin "78") (pinfunction "GND_78") (pintype "power_in"))
      (node (ref "J18") (pin "9") (pinfunction "GND_9") (pintype "power_in"))
      (node (ref "J2") (pin "2") (pinfunction "2_2") (pintype "passive"))
      (node (ref "J2") (pin "3") (pinfunction "3_3") (pintype "passive"))
      (node (ref "J3") (pin "1") (pinfunction "1_1") (pintype "passive"))
      (node (ref "J3") (pin "23") (pinfunction "23_23") (pintype "passive"))
      (node (ref "J3") (pin "3") (pinfunction "3_3") (pintype "passive"))
      (node (ref "J3") (pin "33") (pinfunction "33_33") (pintype "passive"))
      (node (ref "J3") (pin "42") (pinfunction "42_42") (pintype "passive"))
      (node (ref "J3") (pin "5") (pinfunction "5_5") (pintype "passive"))
      (node (ref "J3") (pin "59") (pinfunction "59_59") (pintype "passive"))
      (node (ref "J3") (pin "7") (pinfunction "7_7") (pintype "passive"))
      (node (ref "J3") (pin "9") (pinfunction "9_9") (pintype "passive"))
      (node (ref "J4") (pin "1") (pinfunction "1_1") (pintype "power_in"))
      (node (ref "J5") (pin "P$1") (pinfunction "GND_P$1") (pintype "bidirectional"))
      (node (ref "J6") (pin "10") (pinfunction "GND_10") (pintype "passive"))
      (node (ref "J6") (pin "21") (pinfunction "GND_21") (pintype "passive"))
      (node (ref "J6") (pin "22") (pinfunction "GND_22") (pintype "passive"))
      (node (ref "J6") (pin "9") (pinfunction "GND_9") (pintype "passive"))
      (node (ref "J6") (pin "@10") (pinfunction "GND_@10") (pintype "passive"))
      (node (ref "J6") (pin "@21") (pinfunction "GND_@21") (pintype "passive"))
      (node (ref "J6") (pin "@22") (pinfunction "GND_@22") (pintype "passive"))
      (node (ref "J6") (pin "@9") (pinfunction "GND_@9") (pintype "passive"))
      (node (ref "J6") (pin "P$10") (pinfunction "GND_P$10") (pintype "passive"))
      (node (ref "J6") (pin "P$21") (pinfunction "GND_P$21") (pintype "passive"))
      (node (ref "J6") (pin "P$22") (pinfunction "GND_P$22") (pintype "passive"))
      (node (ref "J6") (pin "P$9") (pinfunction "GND_P$9") (pintype "passive"))
      (node (ref "J7") (pin "P$1") (pinfunction "GND_P$1") (pintype "bidirectional"))
      (node (ref "JTAG") (pin "3") (pinfunction "3_3") (pintype "bidirectional"))
      (node (ref "JTAG") (pin "5") (pinfunction "5_5") (pintype "bidirectional"))
      (node (ref "JTAG") (pin "9") (pinfunction "9_9") (pintype "bidirectional"))
      (node (ref "MODE") (pin "1") (pinfunction "1_1") (pintype "passive"))
      (node (ref "MODE") (pin "2") (pinfunction "2_2") (pintype "passive"))
      (node (ref "MS1") (pin "4") (pinfunction "GND_4") (pintype "power_in"))
      (node (ref "MS1") (pin "4'") (pinfunction "GND_4'") (pintype "power_in"))
      (node (ref "Q1") (pin "2") (pinfunction "2_2") (pintype "bidirectional"))
      (node (ref "R1") (pin "2") (pinfunction "2_2") (pintype "passive"))
      (node (ref "R10") (pin "2") (pinfunction "2_2") (pintype "passive"))
      (node (ref "R17") (pin "1") (pinfunction "1_1") (pintype "passive"))
      (node (ref "R22") (pin "1") (pinfunction "1_1") (pintype "passive"))
      (node (ref "R27") (pin "2") (pinfunction "2_2") (pintype "passive"))
      (node (ref "R28") (pin "2") (pinfunction "2_2") (pintype "passive"))
      (node (ref "R29") (pin "2") (pinfunction "2_2") (pintype "passive"))
      (node (ref "R3") (pin "2") (pinfunction "2_2") (pintype "passive"))
      (node (ref "R37") (pin "2") (pinfunction "2_2") (pintype "bidirectional"))
      (node (ref "R38") (pin "1") (pinfunction "1_1") (pintype "bidirectional"))
      (node (ref "R5") (pin "2") (pinfunction "2_2") (pintype "passive"))
      (node (ref "R6") (pin "2") (pinfunction "2_2") (pintype "passive"))
      (node (ref "R7") (pin "2") (pinfunction "2_2") (pintype "passive"))
      (node (ref "R9") (pin "2") (pinfunction "2_2") (pintype "passive"))
      (node (ref "RESET") (pin "1") (pinfunction "1_1") (pintype "passive"))
      (node (ref "RESET") (pin "2") (pinfunction "2_2") (pintype "passive"))
      (node (ref "RT2") (pin "1") (pinfunction "1_1") (pintype "bidirectional"))
      (node (ref "S1") (pin "2") (pinfunction "2_2") (pintype "bidirectional"))
      (node (ref "S1") (pin "5") (pinfunction "5_5") (pintype "bidirectional"))
      (node (ref "S4") (pin "3") (pinfunction "3_3") (pintype "bidirectional"))
      (node (ref "S4") (pin "6") (pinfunction "6_6") (pintype "bidirectional"))
      (node (ref "TP8") (pin "1") (pinfunction "1_1") (pintype "bidirectional"))
      (node (ref "U1") (pin "2") (pinfunction "VSS_2") (pintype "power_in"))
      (node (ref "U2") (pin "4") (pinfunction "GND_4") (pintype "power_in"))
      (node (ref "U2") (pin "7") (pinfunction "WP_7") (pintype "input"))
      (node (ref "U7") (pin "1") (pinfunction "GND_1") (pintype "power_in"))
      (node (ref "USB1") (pin "GND") (pinfunction "GND_GND") (pintype "bidirectional"))
      (node (ref "USB1") (pin "GND2") (pinfunction "GND_GND2") (pintype "bidirectional"))
      (node (ref "USB2") (pin "GND") (pinfunction "GND_GND") (pintype "bidirectional"))
      (node (ref "USB2") (pin "GND2") (pinfunction "GND_GND2") (pintype "bidirectional"))
      (node (ref "X1") (pin "2") (pinfunction "2_2") (pintype "passive"))
      (node (ref "X1") (pin "3") (pinfunction "2_3") (pintype "passive"))
      (node (ref "X1") (pin "4") (pinfunction "2_4") (pintype "passive"))
      (node (ref "X1") (pin "5") (pinfunction "2_5") (pintype "passive"))
      (node (ref "X2") (pin "2") (pinfunction "2_2") (pintype "passive"))
      (node (ref "X2") (pin "3") (pinfunction "2_3") (pintype "passive"))
      (node (ref "X2") (pin "4") (pinfunction "2_4") (pintype "passive"))
      (node (ref "X2") (pin "5") (pinfunction "2_5") (pintype "passive"))
      (node (ref "X3") (pin "2") (pinfunction "2_2") (pintype "passive"))
      (node (ref "X3") (pin "3") (pinfunction "2_3") (pintype "passive"))
      (node (ref "X3") (pin "4") (pinfunction "2_4") (pintype "passive"))
      (node (ref "X3") (pin "5") (pinfunction "2_5") (pintype "passive"))
      (node (ref "X4") (pin "C") (pinfunction "C_C") (pintype "power_in"))
      (node (ref "X5") (pin "C") (pinfunction "C_C") (pintype "power_in"))
      (node (ref "X6") (pin "C") (pinfunction "C_C") (pintype "power_in"))
    )
    (net (code "16") (name "GPIO0") (class "Default")
      (node (ref "J18") (pin "62") (pinfunction "D22_62") (pintype "bidirectional"))
      (node (ref "J3") (pin "48") (pinfunction "48_48") (pintype "passive"))
      (node (ref "JP26") (pin "2") (pinfunction "2_2") (pintype "passive"))
    )
    (net (code "17") (name "GPIO1") (class "Default")
      (node (ref "J18") (pin "64") (pinfunction "D23_64") (pintype "bidirectional"))
      (node (ref "J3") (pin "50") (pinfunction "50_50") (pintype "passive"))
      (node (ref "J6") (pin "7") (pinfunction "REGN_7") (pintype "passive"))
      (node (ref "J6") (pin "@7") (pinfunction "REGN_@7") (pintype "passive"))
      (node (ref "J6") (pin "P$7") (pinfunction "REGN_P$7") (pintype "passive"))
    )
    (net (code "18") (name "LED_BLUE") (class "Default")
      (node (ref "J18") (pin "65") (pinfunction "RGB_BLUE_65") (pintype "bidirectional"))
      (node (ref "J3") (pin "49") (pinfunction "49_49") (pintype "passive"))
      (node (ref "R8") (pin "1") (pinfunction "1_1") (pintype "passive"))
    )
    (net (code "19") (name "LED_GREEN") (class "Default")
      (node (ref "J18") (pin "63") (pinfunction "RGB_GREEN_63") (pintype "bidirectional"))
      (node (ref "J3") (pin "47") (pinfunction "47_47") (pintype "passive"))
      (node (ref "R19") (pin "1") (pinfunction "1_1") (pintype "passive"))
    )
    (net (code "20") (name "LED_RED") (class "Default")
      (node (ref "J18") (pin "61") (pinfunction "RGB_RED_61") (pintype "bidirectional"))
      (node (ref "J3") (pin "45") (pinfunction "45_45") (pintype "passive"))
      (node (ref "R20") (pin "1") (pinfunction "1_1") (pintype "passive"))
    )
    (net (code "21") (name "MISO") (class "Default")
      (node (ref "J18") (pin "50") (pinfunction "MISO_50") (pintype "bidirectional"))
      (node (ref "J3") (pin "36") (pinfunction "36_36") (pintype "passive"))
      (node (ref "JP14") (pin "1") (pinfunction "1_1") (pintype "passive"))
    )
    (net (code "22") (name "MOSI") (class "Default")
      (node (ref "J18") (pin "52") (pinfunction "MOSI_52") (pintype "bidirectional"))
      (node (ref "J3") (pin "38") (pinfunction "38_38") (pintype "passive"))
      (node (ref "JP13") (pin "1") (pinfunction "1_1") (pintype "passive"))
    )
    (net (code "23") (name "NC") (class "Default")
      (node (ref "MS1") (pin "16") (pinfunction "NC_16") (pintype "passive"))
      (node (ref "MS1") (pin "16'") (pinfunction "NC_16'") (pintype "passive"))
    )
    (net (code "24") (name "NFC1") (class "Default")
      (node (ref "J18") (pin "17") (pinfunction "D21_17") (pintype "bidirectional"))
      (node (ref "J3") (pin "11") (pinfunction "11_11") (pintype "passive"))
      (node (ref "NFC") (pin "2@1") (pinfunction "GND_2@1") (pintype "passive"))
      (node (ref "NFC") (pin "2@2") (pinfunction "GND_2@2") (pintype "passive"))
      (node (ref "R37") (pin "1") (pinfunction "1_1") (pintype "bidirectional"))
    )
    (net (code "25") (name "NFC2") (class "Default")
      (node (ref "J18") (pin "19") (pinfunction "D20_19") (pintype "bidirectional"))
      (node (ref "J3") (pin "13") (pinfunction "13_13") (pintype "passive"))
      (node (ref "NFC") (pin "1") (pinfunction "1_1") (pintype "passive"))
      (node (ref "R38") (pin "2") (pinfunction "2_2") (pintype "bidirectional"))
    )
    (net (code "26") (name "Net-(C2-Pad1)") (class "Default")
      (node (ref "C2") (pin "1") (pinfunction "1_1") (pintype "passive"))
      (node (ref "R5") (pin "1") (pinfunction "1_1") (pintype "passive"))
      (node (ref "USB2") (pin "SHLD1") (pinfunction "SHLD_SHLD1") (pintype "bidirectional"))
      (node (ref "USB2") (pin "SHLD2") (pinfunction "SHLD_SHLD2") (pintype "bidirectional"))
      (node (ref "USB2") (pin "SHLD3") (pinfunction "SHLD_SHLD3") (pintype "bidirectional"))
      (node (ref "USB2") (pin "SHLD4") (pinfunction "SHLD_SHLD4") (pintype "bidirectional"))
      (node (ref "USB2") (pin "SHLD5") (pinfunction "SHLD_SHLD5") (pintype "bidirectional"))
      (node (ref "USB2") (pin "SHLD6") (pinfunction "SHLD_SHLD6") (pintype "bidirectional"))
      (node (ref "USB2") (pin "SHLD7") (pinfunction "SHLD_SHLD7") (pintype "bidirectional"))
      (node (ref "USB2") (pin "SHLD8") (pinfunction "SHLD_SHLD8") (pintype "bidirectional"))
    )
    (net (code "27") (name "Net-(C3-Pad1)") (class "Default")
      (node (ref "C3") (pin "1") (pinfunction "1_1") (pintype "passive"))
      (node (ref "R10") (pin "1") (pinfunction "1_1") (pintype "passive"))
      (node (ref "USB1") (pin "SHLD1") (pinfunction "SHLD_SHLD1") (pintype "bidirectional"))
      (node (ref "USB1") (pin "SHLD2") (pinfunction "SHLD_SHLD2") (pintype "bidirectional"))
      (node (ref "USB1") (pin "SHLD3") (pinfunction "SHLD_SHLD3") (pintype "bidirectional"))
      (node (ref "USB1") (pin "SHLD4") (pinfunction "SHLD_SHLD4") (pintype "bidirectional"))
      (node (ref "USB1") (pin "SHLD5") (pinfunction "SHLD_SHLD5") (pintype "bidirectional"))
      (node (ref "USB1") (pin "SHLD6") (pinfunction "SHLD_SHLD6") (pintype "bidirectional"))
      (node (ref "USB1") (pin "SHLD7") (pinfunction "SHLD_SHLD7") (pintype "bidirectional"))
      (node (ref "USB1") (pin "SHLD8") (pinfunction "SHLD_SHLD8") (pintype "bidirectional"))
    )
    (net (code "28") (name "Net-(D2-P$2)") (class "Default")
      (node (ref "D2") (pin "2") (pinfunction "P$2_2") (pintype "bidirectional"))
      (node (ref "JTAG") (pin "1") (pinfunction "1_1") (pintype "bidirectional"))
    )
    (net (code "29") (name "Net-(D4-PadC)") (class "Default")
      (node (ref "D4") (pin "C") (pinfunction "C_C") (pintype "passive"))
      (node (ref "J1") (pin "1") (pinfunction "1_1") (pintype "passive"))
      (node (ref "R23") (pin "2") (pinfunction "2_2") (pintype "passive"))
    )
    (net (code "30") (name "Net-(D17-PadC)") (class "Default")
      (node (ref "D17") (pin "C") (pinfunction "C_C") (pintype "passive"))
      (node (ref "F5") (pin "1") (pinfunction "1_1") (pintype "passive"))
      (node (ref "J2") (pin "1") (pinfunction "1_1") (pintype "passive"))
    )
    (net (code "31") (name "Net-(F5-Pad2)") (class "Default")
      (node (ref "F5") (pin "2") (pinfunction "2_2") (pintype "passive"))
      (node (ref "Q4") (pin "2") (pinfunction "2_2") (pintype "bidirectional"))
      (node (ref "R14") (pin "2") (pinfunction "2_2") (pintype "passive"))
    )
    (net (code "32") (name "Net-(J1-Pad3)") (class "Default")
      (node (ref "J1") (pin "3") (pinfunction "3_3") (pintype "passive"))
      (node (ref "Q5") (pin "3") (pinfunction "3_3") (pintype "bidirectional"))
    )
    (net (code "33") (name "Net-(J3-Pad29)") (class "Default")
      (node (ref "J3") (pin "29") (pinfunction "29_29") (pintype "passive"))
      (node (ref "JP4") (pin "1") (pinfunction "1_1") (pintype "bidirectional"))
    )
    (net (code "34") (name "Net-(J6-5DC-Pad3)") (class "Default")
      (node (ref "J6") (pin "3") (pinfunction "5DC_3") (pintype "passive"))
      (node (ref "J6") (pin "@3") (pinfunction "5DC_@3") (pintype "passive"))
      (node (ref "J6") (pin "P$3") (pinfunction "5DC_P$3") (pintype "passive"))
    )
    (net (code "35") (name "Net-(J6-5DC-Pad4)") (class "Default")
      (node (ref "J6") (pin "4") (pinfunction "5DC_4") (pintype "passive"))
      (node (ref "J6") (pin "@4") (pinfunction "5DC_@4") (pintype "passive"))
      (node (ref "J6") (pin "P$4") (pinfunction "5DC_P$4") (pintype "passive"))
    )
    (net (code "36") (name "Net-(J6-ENABLE-Pad25)") (class "Default")
      (node (ref "J6") (pin "25") (pinfunction "ENABLE_25") (pintype "passive"))
      (node (ref "J6") (pin "@25") (pinfunction "ENABLE_@25") (pintype "passive"))
      (node (ref "J6") (pin "P$25") (pinfunction "ENABLE_P$25") (pintype "passive"))
    )
    (net (code "37") (name "Net-(J6-PG-Pad24)") (class "Default")
      (node (ref "J6") (pin "24") (pinfunction "PG_24") (pintype "passive"))
      (node (ref "J6") (pin "@24") (pinfunction "PG_@24") (pintype "passive"))
      (node (ref "J6") (pin "P$24") (pinfunction "PG_P$24") (pintype "passive"))
      (node (ref "R21") (pin "1") (pinfunction "1_1") (pintype "passive"))
    )
    (net (code "38") (name "Net-(J12-Pad1)") (class "Default")
      (node (ref "J12") (pin "1") (pinfunction "1_1") (pintype "bidirectional"))
      (node (ref "R24") (pin "1") (pinfunction "1_1") (pintype "passive"))
    )
    (net (code "39") (name "Net-(J18-PadSWCLK)") (class "Default")
      (node (ref "J18") (pin "SWCLK") (pinfunction "SWCLK_SWCLK") (pintype "power_in"))
      (node (ref "JTAG") (pin "4") (pinfunction "4_4") (pintype "bidirectional"))
    )
    (net (code "40") (name "Net-(J18-PadSWDIO)") (class "Default")
      (node (ref "J18") (pin "SWDIO") (pinfunction "SWDIO_SWDIO") (pintype "power_in"))
      (node (ref "JTAG") (pin "2") (pinfunction "2_2") (pintype "bidirectional"))
    )
    (net (code "41") (name "Net-(J18-PadSWO)") (class "Default")
      (node (ref "J18") (pin "SWO") (pinfunction "SWO_SWO") (pintype "power_in"))
      (node (ref "JTAG") (pin "6") (pinfunction "6_6") (pintype "bidirectional"))
    )
    (net (code "42") (name "Net-(J19-Pad1)") (class "Default")
      (node (ref "J19") (pin "1") (pinfunction "1_1") (pintype "bidirectional"))
      (node (ref "R25") (pin "1") (pinfunction "1_1") (pintype "passive"))
    )
    (net (code "43") (name "Net-(J20-Pad1)") (class "Default")
      (node (ref "J20") (pin "1") (pinfunction "1_1") (pintype "bidirectional"))
      (node (ref "R26") (pin "1") (pinfunction "1_1") (pintype "passive"))
    )
    (net (code "44") (name "Net-(J21-Pad2)") (class "Default")
      (node (ref "J21") (pin "2") (pinfunction "2_2") (pintype "bidirectional"))
      (node (ref "RT1") (pin "1") (pinfunction "1_1") (pintype "bidirectional"))
      (node (ref "RT2") (pin "2") (pinfunction "2_2") (pintype "bidirectional"))
      (node (ref "TP2") (pin "1") (pinfunction "1_1") (pintype "bidirectional"))
      (node (ref "TP5") (pin "1") (pinfunction "1_1") (pintype "bidirectional"))
    )
    (net (code "45") (name "Net-(JP1-Pad1)") (class "Default")
      (node (ref "JP1") (pin "1") (pinfunction "1_1") (pintype "bidirectional"))
      (node (ref "R27") (pin "1") (pinfunction "1_1") (pintype "passive"))
    )
    (net (code "46") (name "Net-(JP2-Pad1)") (class "Default")
      (node (ref "JP2") (pin "1") (pinfunction "1_1") (pintype "bidirectional"))
      (node (ref "R28") (pin "1") (pinfunction "1_1") (pintype "passive"))
    )
    (net (code "47") (name "Net-(JP3-Pad1)") (class "Default")
      (node (ref "JP3") (pin "1") (pinfunction "1_1") (pintype "bidirectional"))
      (node (ref "R29") (pin "1") (pinfunction "1_1") (pintype "passive"))
    )
    (net (code "48") (name "Net-(JP5-Pad2)") (class "Default")
      (node (ref "JP5") (pin "2") (pinfunction "2_2") (pintype "passive"))
      (node (ref "MS1") (pin "1") (pinfunction "~{RST}_1") (pintype "input"))
      (node (ref "MS1") (pin "1'") (pinfunction "~{RST}_1'") (pintype "input"))
    )
    (net (code "49") (name "Net-(JP6-Pad2)") (class "Default")
      (node (ref "JP6") (pin "2") (pinfunction "2_2") (pintype "passive"))
      (node (ref "MS1") (pin "5") (pinfunction "A0_5") (pintype "bidirectional"))
      (node (ref "MS1") (pin "5'") (pinfunction "A0_5'") (pintype "bidirectional"))
    )
    (net (code "50") (name "Net-(JP7-Pad2)") (class "Default")
      (node (ref "JP7") (pin "2") (pinfunction "2_2") (pintype "passive"))
      (node (ref "MS1") (pin "6") (pinfunction "A1_6") (pintype "bidirectional"))
      (node (ref "MS1") (pin "6'") (pinfunction "A1_6'") (pintype "bidirectional"))
    )
    (net (code "51") (name "Net-(JP8-Pad2)") (class "Default")
      (node (ref "JP8") (pin "2") (pinfunction "2_2") (pintype "passive"))
      (node (ref "MS1") (pin "7") (pinfunction "A2_7") (pintype "bidirectional"))
      (node (ref "MS1") (pin "7'") (pinfunction "A2_7'") (pintype "bidirectional"))
    )
    (net (code "52") (name "Net-(JP9-Pad2)") (class "Default")
      (node (ref "JP9") (pin "2") (pinfunction "2_2") (pintype "passive"))
      (node (ref "MS1") (pin "8") (pinfunction "A3_8") (pintype "bidirectional"))
      (node (ref "MS1") (pin "8'") (pinfunction "A3_8'") (pintype "bidirectional"))
    )
    (net (code "53") (name "Net-(JP10-Pad2)") (class "Default")
      (node (ref "JP10") (pin "2") (pinfunction "2_2") (pintype "passive"))
      (node (ref "MS1") (pin "9") (pinfunction "A4_9") (pintype "bidirectional"))
      (node (ref "MS1") (pin "9'") (pinfunction "A4_9'") (pintype "bidirectional"))
    )
    (net (code "54") (name "Net-(JP11-Pad2)") (class "Default")
      (node (ref "JP11") (pin "2") (pinfunction "2_2") (pintype "passive"))
      (node (ref "MS1") (pin "10") (pinfunction "A5_10") (pintype "bidirectional"))
      (node (ref "MS1") (pin "10'") (pinfunction "A5_10'") (pintype "bidirectional"))
    )
    (net (code "55") (name "Net-(JP12-Pad2)") (class "Default")
      (node (ref "JP12") (pin "2") (pinfunction "2_2") (pintype "passive"))
      (node (ref "MS1") (pin "11") (pinfunction "SCK_11") (pintype "bidirectional"))
      (node (ref "MS1") (pin "11'") (pinfunction "SCK_11'") (pintype "bidirectional"))
    )
    (net (code "56") (name "Net-(JP13-Pad2)") (class "Default")
      (node (ref "JP13") (pin "2") (pinfunction "2_2") (pintype "passive"))
      (node (ref "MS1") (pin "12") (pinfunction "MOSI_12") (pintype "bidirectional"))
      (node (ref "MS1") (pin "12'") (pinfunction "MOSI_12'") (pintype "bidirectional"))
    )
    (net (code "57") (name "Net-(JP14-Pad2)") (class "Default")
      (node (ref "JP14") (pin "2") (pinfunction "2_2") (pintype "passive"))
      (node (ref "MS1") (pin "13") (pinfunction "MISO_13") (pintype "bidirectional"))
      (node (ref "MS1") (pin "13'") (pinfunction "MISO_13'") (pintype "bidirectional"))
    )
    (net (code "58") (name "Net-(JP15-Pad2)") (class "Default")
      (node (ref "JP15") (pin "2") (pinfunction "2_2") (pintype "passive"))
      (node (ref "MS1") (pin "14") (pinfunction "RX_14") (pintype "bidirectional"))
      (node (ref "MS1") (pin "14'") (pinfunction "RX_14'") (pintype "bidirectional"))
    )
    (net (code "59") (name "Net-(JP16-Pad2)") (class "Default")
      (node (ref "JP16") (pin "2") (pinfunction "2_2") (pintype "passive"))
      (node (ref "MS1") (pin "15") (pinfunction "TX_15") (pintype "bidirectional"))
      (node (ref "MS1") (pin "15'") (pinfunction "TX_15'") (pintype "bidirectional"))
    )
    (net (code "60") (name "Net-(JP17-Pad1)") (class "Default")
      (node (ref "JP17") (pin "1") (pinfunction "1_1") (pintype "passive"))
      (node (ref "MS1") (pin "28") (pinfunction "LI+_28") (pintype "power_in"))
      (node (ref "MS1") (pin "28'") (pinfunction "LI+_28'") (pintype "power_in"))
    )
    (net (code "61") (name "Net-(JP19-Pad1)") (class "Default")
      (node (ref "JP19") (pin "1") (pinfunction "1_1") (pintype "passive"))
      (node (ref "MS1") (pin "26") (pinfunction "VUSB_26") (pintype "power_in"))
      (node (ref "MS1") (pin "26'") (pinfunction "VUSB_26'") (pintype "power_in"))
    )
    (net (code "62") (name "Net-(JP20-Pad1)") (class "Default")
      (node (ref "JP20") (pin "1") (pinfunction "1_1") (pintype "passive"))
      (node (ref "MS1") (pin "25") (pinfunction "D8_25") (pintype "bidirectional"))
      (node (ref "MS1") (pin "25'") (pinfunction "D8_25'") (pintype "bidirectional"))
    )
    (net (code "63") (name "Net-(JP21-Pad1)") (class "Default")
      (node (ref "JP21") (pin "1") (pinfunction "1_1") (pintype "passive"))
      (node (ref "MS1") (pin "24") (pinfunction "D7_24") (pintype "bidirectional"))
      (node (ref "MS1") (pin "24'") (pinfunction "D7_24'") (pintype "bidirectional"))
    )
    (net (code "64") (name "Net-(JP22-Pad1)") (class "Default")
      (node (ref "JP22") (pin "1") (pinfunction "1_1") (pintype "passive"))
      (node (ref "MS1") (pin "23") (pinfunction "D6_23") (pintype "bidirectional"))
      (node (ref "MS1") (pin "23'") (pinfunction "D6_23'") (pintype "bidirectional"))
    )
    (net (code "65") (name "Net-(JP23-Pad1)") (class "Default")
      (node (ref "JP23") (pin "1") (pinfunction "1_1") (pintype "passive"))
      (node (ref "MS1") (pin "22") (pinfunction "D5_22") (pintype "bidirectional"))
      (node (ref "MS1") (pin "22'") (pinfunction "D5_22'") (pintype "bidirectional"))
    )
    (net (code "66") (name "Net-(JP24-Pad1)") (class "Default")
      (node (ref "JP24") (pin "1") (pinfunction "1_1") (pintype "passive"))
      (node (ref "MS1") (pin "21") (pinfunction "D4_21") (pintype "bidirectional"))
      (node (ref "MS1") (pin "21'") (pinfunction "D4_21'") (pintype "bidirectional"))
    )
    (net (code "67") (name "Net-(JP25-Pad1)") (class "Default")
      (node (ref "JP25") (pin "1") (pinfunction "1_1") (pintype "passive"))
      (node (ref "MS1") (pin "20") (pinfunction "D3_20") (pintype "bidirectional"))
      (node (ref "MS1") (pin "20'") (pinfunction "D3_20'") (pintype "bidirectional"))
    )
    (net (code "68") (name "Net-(JP26-Pad1)") (class "Default")
      (node (ref "JP26") (pin "1") (pinfunction "1_1") (pintype "passive"))
      (node (ref "MS1") (pin "19") (pinfunction "D2_19") (pintype "bidirectional"))
      (node (ref "MS1") (pin "19'") (pinfunction "D2_19'") (pintype "bidirectional"))
    )
    (net (code "69") (name "Net-(JP27-Pad1)") (class "Default")
      (node (ref "JP27") (pin "1") (pinfunction "1_1") (pintype "passive"))
      (node (ref "MS1") (pin "18") (pinfunction "SCL_18") (pintype "bidirectional"))
      (node (ref "MS1") (pin "18'") (pinfunction "SCL_18'") (pintype "bidirectional"))
    )
    (net (code "70") (name "Net-(JP28-Pad1)") (class "Default")
      (node (ref "JP28") (pin "1") (pinfunction "1_1") (pintype "passive"))
      (node (ref "MS1") (pin "17") (pinfunction "SDA_17") (pintype "bidirectional"))
      (node (ref "MS1") (pin "17'") (pinfunction "SDA_17'") (pintype "bidirectional"))
    )
    (net (code "71") (name "Net-(LED1-A)") (class "Default")
      (node (ref "LED1") (pin "1") (pinfunction "A_1") (pintype "bidirectional"))
      (node (ref "R16") (pin "2") (pinfunction "2_2") (pintype "passive"))
      (node (ref "R18") (pin "1") (pinfunction "1_1") (pintype "passive"))
    )
    (net (code "72") (name "Net-(LED1-K)") (class "Default")
      (node (ref "LED1") (pin "2") (pinfunction "K_2") (pintype "bidirectional"))
      (node (ref "Q1") (pin "3") (pinfunction "3_3") (pintype "bidirectional"))
      (node (ref "R22") (pin "2") (pinfunction "2_2") (pintype "passive"))
    )
    (net (code "73") (name "Net-(LED3-K)") (class "Default")
      (node (ref "LED3") (pin "2") (pinfunction "K_2") (pintype "bidirectional"))
      (node (ref "R13") (pin "1") (pinfunction "1_1") (pintype "bidirectional"))
    )
    (net (code "74") (name "Net-(MS1-MD-Pad3')") (class "Default")
      (node (ref "MS1") (pin "3") (pinfunction "MD_3") (pintype "bidirectional"))
      (node (ref "MS1") (pin "3'") (pinfunction "MD_3'") (pintype "bidirectional"))
    )
    (net (code "75") (name "Net-(Q1-Pad1)") (class "Default")
      (node (ref "Q1") (pin "1") (pinfunction "1_1") (pintype "bidirectional"))
      (node (ref "R11") (pin "1") (pinfunction "1_1") (pintype "passive"))
      (node (ref "R17") (pin "2") (pinfunction "2_2") (pintype "passive"))
    )
    (net (code "76") (name "Net-(Q3-Pad1)") (class "Default")
      (node (ref "Q3") (pin "1") (pinfunction "1_1") (pintype "bidirectional"))
      (node (ref "Q5") (pin "1") (pinfunction "1_1") (pintype "bidirectional"))
      (node (ref "R30") (pin "1") (pinfunction "1_1") (pintype "bidirectional"))
      (node (ref "R31") (pin "1") (pinfunction "1_1") (pintype "bidirectional"))
    )
    (net (code "77") (name "Net-(Q3-Pad2)") (class "Default")
      (node (ref "Q3") (pin "2") (pinfunction "2_2") (pintype "bidirectional"))
      (node (ref "Q5") (pin "2") (pinfunction "2_2") (pintype "bidirectional"))
      (node (ref "R30") (pin "2") (pinfunction "2_2") (pintype "bidirectional"))
      (node (ref "R33") (pin "2") (pinfunction "2_2") (pintype "bidirectional"))
    )
    (net (code "78") (name "Net-(Q4-Pad1)") (class "Default")
      (node (ref "Q4") (pin "1") (pinfunction "1_1") (pintype "bidirectional"))
      (node (ref "R14") (pin "1") (pinfunction "1_1") (pintype "passive"))
      (node (ref "R15") (pin "2") (pinfunction "2_2") (pintype "passive"))
    )
    (net (code "79") (name "Net-(R15-Pad1)") (class "Default")
      (node (ref "R15") (pin "1") (pinfunction "1_1") (pintype "passive"))
      (node (ref "S1") (pin "3") (pinfunction "3_3") (pintype "bidirectional"))
      (node (ref "S1") (pin "6") (pinfunction "6_6") (pintype "bidirectional"))
    )
    (net (code "80") (name "Net-(R31-Pad2)") (class "Default")
      (node (ref "R31") (pin "2") (pinfunction "2_2") (pintype "bidirectional"))
      (node (ref "S4") (pin "2") (pinfunction "2_2") (pintype "bidirectional"))
      (node (ref "S4") (pin "5") (pinfunction "5_5") (pintype "bidirectional"))
    )
    (net (code "81") (name "Net-(R33-Pad1)") (class "Default")
      (node (ref "R33") (pin "1") (pinfunction "1_1") (pintype "bidirectional"))
      (node (ref "S4") (pin "1") (pinfunction "1_1") (pintype "bidirectional"))
      (node (ref "S4") (pin "4") (pinfunction "4_4") (pintype "bidirectional"))
    )
    (net (code "82") (name "Net-(RGB-2)") (class "Default")
      (node (ref "R8") (pin "2") (pinfunction "2_2") (pintype "passive"))
      (node (ref "RGB") (pin "BLUE") (pinfunction "2_BLUE") (pintype "passive"))
    )
    (net (code "83") (name "Net-(RGB-3)") (class "Default")
      (node (ref "R19") (pin "2") (pinfunction "2_2") (pintype "passive"))
      (node (ref "RGB") (pin "GREEN") (pinfunction "3_GREEN") (pintype "passive"))
    )
    (net (code "84") (name "Net-(RGB-4)") (class "Default")
      (node (ref "R20") (pin "2") (pinfunction "2_2") (pintype "passive"))
      (node (ref "RGB") (pin "RED") (pinfunction "4_RED") (pintype "passive"))
    )
    (net (code "85") (name "Net-(S1-Pad1)") (class "Default")
      (node (ref "S1") (pin "1") (pinfunction "1_1") (pintype "bidirectional"))
      (node (ref "S1") (pin "4") (pinfunction "4_4") (pintype "bidirectional"))
    )
    (net (code "86") (name "Net-(U1-CE)") (class "Default")
      (node (ref "R2") (pin "1") (pinfunction "1_1") (pintype "passive"))
      (node (ref "R7") (pin "1") (pinfunction "1_1") (pintype "passive"))
      (node (ref "U1") (pin "4") (pinfunction "CE_4") (pintype "bidirectional"))
    )
    (net (code "87") (name "Net-(U2-A0)") (class "Default")
      (node (ref "J20") (pin "2") (pinfunction "2_2") (pintype "bidirectional"))
      (node (ref "JP3") (pin "2") (pinfunction "2_2") (pintype "bidirectional"))
      (node (ref "U2") (pin "1") (pinfunction "A0_1") (pintype "input"))
    )
    (net (code "88") (name "Net-(U2-A1)") (class "Default")
      (node (ref "J19") (pin "2") (pinfunction "2_2") (pintype "bidirectional"))
      (node (ref "JP2") (pin "2") (pinfunction "2_2") (pintype "bidirectional"))
      (node (ref "U2") (pin "2") (pinfunction "A1_2") (pintype "input"))
    )
    (net (code "89") (name "Net-(U2-A2)") (class "Default")
      (node (ref "J12") (pin "2") (pinfunction "2_2") (pintype "bidirectional"))
      (node (ref "JP1") (pin "2") (pinfunction "2_2") (pintype "bidirectional"))
      (node (ref "U2") (pin "3") (pinfunction "A2_3") (pintype "input"))
    )
    (net (code "90") (name "Net-(USB1-CC1)") (class "Default")
      (node (ref "R6") (pin "1") (pinfunction "1_1") (pintype "passive"))
      (node (ref "USB1") (pin "A5") (pinfunction "CC1_A5") (pintype "bidirectional"))
    )
    (net (code "91") (name "Net-(USB1-CC2)") (class "Default")
      (node (ref "R9") (pin "1") (pinfunction "1_1") (pintype "passive"))
      (node (ref "USB1") (pin "B5") (pinfunction "CC2_B5") (pintype "bidirectional"))
    )
    (net (code "92") (name "Net-(USB2-CC1)") (class "Default")
      (node (ref "R1") (pin "1") (pinfunction "1_1") (pintype "passive"))
      (node (ref "USB2") (pin "A5") (pinfunction "CC1_A5") (pintype "bidirectional"))
    )
    (net (code "93") (name "Net-(USB2-CC2)") (class "Default")
      (node (ref "R3") (pin "1") (pinfunction "1_1") (pintype "passive"))
      (node (ref "USB2") (pin "B5") (pinfunction "CC2_B5") (pintype "bidirectional"))
    )
    (net (code "94") (name "PWM0") (class "Default")
      (node (ref "J18") (pin "66") (pinfunction "D4_66") (pintype "bidirectional"))
      (node (ref "J3") (pin "52") (pinfunction "52_52") (pintype "passive"))
      (node (ref "JP24") (pin "2") (pinfunction "2_2") (pintype "passive"))
    )
    (net (code "95") (name "PWM1") (class "Default")
      (node (ref "J18") (pin "68") (pinfunction "D5_68") (pintype "bidirectional"))
      (node (ref "J3") (pin "54") (pinfunction "54_54") (pintype "passive"))
      (node (ref "JP20") (pin "2") (pinfunction "2_2") (pintype "passive"))
    )
    (net (code "96") (name "PWM2") (class "Default")
      (node (ref "J18") (pin "70") (pinfunction "D6_70") (pintype "bidirectional"))
      (node (ref "J3") (pin "56") (pinfunction "56_56") (pintype "passive"))
      (node (ref "JP22") (pin "2") (pinfunction "2_2") (pintype "passive"))
    )
    (net (code "97") (name "PWM3") (class "Default")
      (node (ref "J18") (pin "72") (pinfunction "D7_72") (pintype "bidirectional"))
      (node (ref "J3") (pin "58") (pinfunction "58_58") (pintype "passive"))
      (node (ref "JP21") (pin "2") (pinfunction "2_2") (pintype "passive"))
    )
    (net (code "98") (name "REGN") (class "Default")
      (node (ref "J6") (pin "8") (pinfunction "NC_8") (pintype "passive"))
      (node (ref "J6") (pin "@8") (pinfunction "NC_@8") (pintype "passive"))
      (node (ref "J6") (pin "P$8") (pinfunction "NC_P$8") (pintype "passive"))
      (node (ref "RT1") (pin "2") (pinfunction "2_2") (pintype "bidirectional"))
      (node (ref "TP1") (pin "1") (pinfunction "1_1") (pintype "bidirectional"))
    )
    (net (code "99") (name "RTS") (class "Default")
      (node (ref "J18") (pin "42") (pinfunction "RTS_42") (pintype "bidirectional"))
      (node (ref "J3") (pin "28") (pinfunction "28_28") (pintype "passive"))
    )
    (net (code "100") (name "RX") (class "Default")
      (node (ref "J18") (pin "38") (pinfunction "RXD_38") (pintype "bidirectional"))
      (node (ref "J3") (pin "24") (pinfunction "24_24") (pintype "passive"))
      (node (ref "JP15") (pin "1") (pinfunction "1_1") (pintype "passive"))
    )
    (net (code "101") (name "SCK") (class "Default")
      (node (ref "J18") (pin "54") (pinfunction "SCLK_54") (pintype "bidirectional"))
      (node (ref "J3") (pin "40") (pinfunction "40_40") (pintype "passive"))
      (node (ref "JP12") (pin "1") (pinfunction "1_1") (pintype "passive"))
    )
    (net (code "102") (name "SCL") (class "Default")
      (node (ref "J18") (pin "20") (pinfunction "SCL_20") (pintype "bidirectional"))
      (node (ref "J3") (pin "14") (pinfunction "14_14") (pintype "passive"))
      (node (ref "J4") (pin "4") (pinfunction "4_4") (pintype "passive"))
      (node (ref "J6") (pin "14") (pinfunction "SCL_14") (pintype "passive"))
      (node (ref "J6") (pin "@14") (pinfunction "SCL_@14") (pintype "passive"))
      (node (ref "J6") (pin "P$14") (pinfunction "SCL_P$14") (pintype "passive"))
      (node (ref "JP27") (pin "2") (pinfunction "2_2") (pintype "passive"))
      (node (ref "U2") (pin "6") (pinfunction "SCL_6") (pintype "input"))
    )
    (net (code "103") (name "SDA") (class "Default")
      (node (ref "J18") (pin "22") (pinfunction "SDA_22") (pintype "bidirectional"))
      (node (ref "J3") (pin "16") (pinfunction "16_16") (pintype "passive"))
      (node (ref "J4") (pin "3") (pinfunction "3_3") (pintype "passive"))
      (node (ref "J6") (pin "15") (pinfunction "SDA_15") (pintype "passive"))
      (node (ref "J6") (pin "@15") (pinfunction "SDA_@15") (pintype "passive"))
      (node (ref "J6") (pin "P$15") (pinfunction "SDA_P$15") (pintype "passive"))
      (node (ref "JP28") (pin "2") (pinfunction "2_2") (pintype "passive"))
      (node (ref "U2") (pin "5") (pinfunction "SDA_5") (pintype "bidirectional"))
    )
    (net (code "104") (name "SOM5") (class "Default")
      (node (ref "C7") (pin "1") (pinfunction "1_1") (pintype "passive"))
      (node (ref "D7") (pin "2") (pinfunction "2_2") (pintype "bidirectional"))
      (node (ref "J13") (pin "C1") (pinfunction "VCC_C1") (pintype "passive"))
      (node (ref "J18") (pin "67") (pinfunction "SIM_VCC_67") (pintype "power_in"))
      (node (ref "J3") (pin "51") (pinfunction "51_51") (pintype "passive"))
      (node (ref "U7") (pin "8") (pinfunction "VCC_8") (pintype "power_in"))
    )
    (net (code "105") (name "SOM6") (class "Default")
      (node (ref "C4") (pin "1") (pinfunction "1_1") (pintype "passive"))
      (node (ref "D13") (pin "2") (pinfunction "2_2") (pintype "bidirectional"))
      (node (ref "J13") (pin "C2") (pinfunction "RST_C2") (pintype "passive"))
      (node (ref "J18") (pin "69") (pinfunction "SIM_RST_69") (pintype "bidirectional"))
      (node (ref "J3") (pin "53") (pinfunction "53_53") (pintype "passive"))
      (node (ref "U7") (pin "7") (pinfunction "RST_7") (pintype "bidirectional"))
    )
    (net (code "106") (name "SOM7") (class "Default")
      (node (ref "C6") (pin "1") (pinfunction "1_1") (pintype "passive"))
      (node (ref "D11") (pin "2") (pinfunction "2_2") (pintype "bidirectional"))
      (node (ref "J13") (pin "C3") (pinfunction "CLK_C3") (pintype "passive"))
      (node (ref "J18") (pin "71") (pinfunction "SIM_CLK_71") (pintype "bidirectional"))
      (node (ref "J3") (pin "55") (pinfunction "55_55") (pintype "passive"))
      (node (ref "U7") (pin "6") (pinfunction "CLK_6") (pintype "bidirectional"))
    )
    (net (code "107") (name "SOM8") (class "Default")
      (node (ref "C5") (pin "1") (pinfunction "1_1") (pintype "passive"))
      (node (ref "D12") (pin "2") (pinfunction "2_2") (pintype "bidirectional"))
      (node (ref "J13") (pin "C7") (pinfunction "I/O_C7") (pintype "passive"))
      (node (ref "J18") (pin "73") (pinfunction "SIM_DATA_73") (pintype "bidirectional"))
      (node (ref "J3") (pin "57") (pinfunction "57_57") (pintype "passive"))
      (node (ref "U7") (pin "3") (pinfunction "IO_3") (pintype "bidirectional"))
    )
    (net (code "108") (name "SOM9") (class "Default")
      (node (ref "J18") (pin "75") (pinfunction "NC_75") (pintype "bidirectional"))
      (node (ref "J3") (pin "60") (pinfunction "60_60") (pintype "passive"))
    )
    (net (code "109") (name "SOM10") (class "Default")
      (node (ref "J18") (pin "14") (pinfunction "NC_14") (pintype "bidirectional"))
      (node (ref "J3") (pin "10") (pinfunction "10_10") (pintype "passive"))
    )
    (net (code "110") (name "SOM11") (class "Default")
      (node (ref "J18") (pin "18") (pinfunction "GNSS_TXD_18") (pintype "bidirectional"))
      (node (ref "J3") (pin "12") (pinfunction "12_12") (pintype "passive"))
    )
    (net (code "111") (name "SOM12") (class "Default")
      (node (ref "J18") (pin "58") (pinfunction "D24_58") (pintype "bidirectional"))
      (node (ref "J3") (pin "44") (pinfunction "44_44") (pintype "passive"))
    )
    (net (code "112") (name "SOM13") (class "Default")
      (node (ref "J18") (pin "60") (pinfunction "D25_60") (pintype "bidirectional"))
      (node (ref "J3") (pin "46") (pinfunction "46_46") (pintype "passive"))
    )
    (net (code "113") (name "SOM14") (class "Default")
      (node (ref "J18") (pin "51") (pinfunction "NC_51") (pintype "bidirectional"))
      (node (ref "J3") (pin "35") (pinfunction "35_35") (pintype "passive"))
    )
    (net (code "114") (name "SOM15") (class "Default")
      (node (ref "J18") (pin "53") (pinfunction "SWD_CLK_53") (pintype "bidirectional"))
      (node (ref "J3") (pin "37") (pinfunction "37_37") (pintype "passive"))
    )
    (net (code "115") (name "SOM16") (class "Default")
      (node (ref "J18") (pin "55") (pinfunction "SWD_DATA_55") (pintype "bidirectional"))
      (node (ref "J3") (pin "39") (pinfunction "39_39") (pintype "passive"))
    )
    (net (code "116") (name "SOM17") (class "Default")
      (node (ref "J18") (pin "57") (pinfunction "D27_57") (pintype "bidirectional"))
      (node (ref "J3") (pin "41") (pinfunction "41_41") (pintype "bidirectional"))
    )
    (net (code "117") (name "SOM18") (class "Default")
      (node (ref "J18") (pin "59") (pinfunction "D26_59") (pintype "bidirectional"))
      (node (ref "J3") (pin "43") (pinfunction "43_43") (pintype "passive"))
    )
    (net (code "118") (name "TS") (class "Default")
      (node (ref "J21") (pin "1") (pinfunction "1_1") (pintype "bidirectional"))
      (node (ref "J6") (pin "17") (pinfunction "TS_17") (pintype "passive"))
      (node (ref "J6") (pin "@17") (pinfunction "TS_@17") (pintype "passive"))
      (node (ref "J6") (pin "P$17") (pinfunction "TS_P$17") (pintype "passive"))
      (node (ref "R23") (pin "1") (pinfunction "1_1") (pintype "passive"))
    )
    (net (code "119") (name "TX") (class "Default")
      (node (ref "J18") (pin "36") (pinfunction "TXD_36") (pintype "bidirectional"))
      (node (ref "J3") (pin "22") (pinfunction "22_22") (pintype "passive"))
      (node (ref "JP16") (pin "1") (pinfunction "1_1") (pintype "passive"))
    )
    (net (code "120") (name "UB_USB_N") (class "Default")
      (node (ref "D23") (pin "1") (pinfunction "1_1") (pintype "bidirectional"))
      (node (ref "J18") (pin "46") (pinfunction "UB_USB_N_46") (pintype "bidirectional"))
      (node (ref "USB2") (pin "A7") (pinfunction "D-_A7") (pintype "bidirectional"))
      (node (ref "USB2") (pin "B7") (pinfunction "D-_B7") (pintype "bidirectional"))
    )
    (net (code "121") (name "UB_USB_P") (class "Default")
      (node (ref "D23") (pin "4") (pinfunction "4_4") (pintype "bidirectional"))
      (node (ref "J18") (pin "44") (pinfunction "UB_USB_P_44") (pintype "bidirectional"))
      (node (ref "USB2") (pin "A6") (pinfunction "D+_A6") (pintype "bidirectional"))
      (node (ref "USB2") (pin "B6") (pinfunction "D+_B6") (pintype "bidirectional"))
    )
    (net (code "122") (name "UB_VBUS") (class "Default")
      (node (ref "D23") (pin "5") (pinfunction "5_5") (pintype "bidirectional"))
      (node (ref "F4") (pin "P$2") (pinfunction "2_P$2") (pintype "bidirectional"))
      (node (ref "USB2") (pin "VBUS1") (pinfunction "VBUS_VBUS1") (pintype "bidirectional"))
      (node (ref "USB2") (pin "VBUS2") (pinfunction "VBUS_VBUS2") (pintype "bidirectional"))
    )
    (net (code "123") (name "UB_VBUS1") (class "Default")
      (node (ref "F4") (pin "P$1") (pinfunction "1_P$1") (pintype "bidirectional"))
      (node (ref "J18") (pin "74") (pinfunction "MODEM_VBUS_74") (pintype "power_in"))
    )
    (net (code "124") (name "USB_N") (class "Default")
      (node (ref "D1") (pin "1") (pinfunction "1_1") (pintype "bidirectional"))
      (node (ref "J18") (pin "13") (pinfunction "USB_N_13") (pintype "bidirectional"))
      (node (ref "USB1") (pin "A7") (pinfunction "D-_A7") (pintype "bidirectional"))
      (node (ref "USB1") (pin "B7") (pinfunction "D-_B7") (pintype "bidirectional"))
    )
    (net (code "125") (name "USB_P") (class "Default")
      (node (ref "D1") (pin "4") (pinfunction "4_4") (pintype "bidirectional"))
      (node (ref "J18") (pin "11") (pinfunction "USB_P_11") (pintype "bidirectional"))
      (node (ref "USB1") (pin "A6") (pinfunction "D+_A6") (pintype "bidirectional"))
      (node (ref "USB1") (pin "B6") (pinfunction "D+_B6") (pintype "bidirectional"))
    )
    (net (code "126") (name "VBAT") (class "Default")
      (node (ref "J6") (pin "18") (pinfunction "VBAT_18") (pintype "passive"))
      (node (ref "J6") (pin "19") (pinfunction "VBAT_19") (pintype "passive"))
      (node (ref "J6") (pin "20") (pinfunction "VBAT_20") (pintype "passive"))
      (node (ref "J6") (pin "@18") (pinfunction "VBAT_@18") (pintype "passive"))
      (node (ref "J6") (pin "@19") (pinfunction "VBAT_@19") (pintype "passive"))
      (node (ref "J6") (pin "@20") (pinfunction "VBAT_@20") (pintype "passive"))
      (node (ref "J6") (pin "P$18") (pinfunction "VBAT_P$18") (pintype "passive"))
      (node (ref "J6") (pin "P$19") (pinfunction "VBAT_P$19") (pintype "passive"))
      (node (ref "J6") (pin "P$20") (pinfunction "VBAT_P$20") (pintype "passive"))
      (node (ref "JP17") (pin "2") (pinfunction "2_2") (pintype "passive"))
      (node (ref "Q3") (pin "3") (pinfunction "3_3") (pintype "bidirectional"))
      (node (ref "VBAT") (pin "1") (pinfunction "TP_1") (pintype "bidirectional"))
    )
    (net (code "127") (name "VBUS") (class "Default")
      (node (ref "F2") (pin "P$2") (pinfunction "2_P$2") (pintype "bidirectional"))
      (node (ref "U1") (pin "5") (pinfunction "VIN_5") (pintype "power_in"))
    )
    (net (code "128") (name "VCC") (class "Default")
      (node (ref "C10") (pin "1") (pinfunction "1_1") (pintype "passive"))
      (node (ref "C20") (pin "1") (pinfunction "1_1") (pintype "passive"))
      (node (ref "C61") (pin "1") (pinfunction "1_1") (pintype "passive"))
      (node (ref "C8") (pin "1") (pinfunction "1_1") (pintype "passive"))
      (node (ref "C9") (pin "1") (pinfunction "1_1") (pintype "passive"))
      (node (ref "D16") (pin "2") (pinfunction "P$2_2") (pintype "bidirectional"))
      (node (ref "J18") (pin "2") (pinfunction "VCC_2") (pintype "power_in"))
      (node (ref "J18") (pin "4") (pinfunction "VCC_4") (pintype "power_in"))
      (node (ref "J18") (pin "6") (pinfunction "VCC_6") (pintype "power_in"))
      (node (ref "J18") (pin "8") (pinfunction "VCC_8") (pintype "power_in"))
      (node (ref "J3") (pin "2") (pinfunction "2_2") (pintype "passive"))
      (node (ref "J3") (pin "4") (pinfunction "4_4") (pintype "passive"))
      (node (ref "J3") (pin "6") (pinfunction "6_6") (pintype "passive"))
      (node (ref "J6") (pin "5") (pinfunction "VCC_5") (pintype "passive"))
      (node (ref "J6") (pin "6") (pinfunction "VCC_6") (pintype "passive"))
      (node (ref "J6") (pin "@5") (pinfunction "VCC_@5") (pintype "passive"))
      (node (ref "J6") (pin "@6") (pinfunction "VCC_@6") (pintype "passive"))
      (node (ref "J6") (pin "P$5") (pinfunction "VCC_P$5") (pintype "passive"))
      (node (ref "J6") (pin "P$6") (pinfunction "VCC_P$6") (pintype "passive"))
      (node (ref "VCC") (pin "1") (pinfunction "TP_1") (pintype "bidirectional"))
    )
    (net (code "129") (name "VIN") (class "Default")
      (node (ref "J6") (pin "11") (pinfunction "VIN_11") (pintype "passive"))
      (node (ref "J6") (pin "12") (pinfunction "VIN_12") (pintype "passive"))
      (node (ref "J6") (pin "@11") (pinfunction "VIN_@11") (pintype "passive"))
      (node (ref "J6") (pin "@12") (pinfunction "VIN_@12") (pintype "passive"))
      (node (ref "J6") (pin "P$11") (pinfunction "VIN_P$11") (pintype "passive"))
      (node (ref "J6") (pin "P$12") (pinfunction "VIN_P$12") (pintype "passive"))
      (node (ref "Q4") (pin "3") (pinfunction "3_3") (pintype "bidirectional"))
      (node (ref "R11") (pin "2") (pinfunction "2_2") (pintype "passive"))
      (node (ref "R18") (pin "2") (pinfunction "2_2") (pintype "passive"))
      (node (ref "VIN") (pin "1") (pinfunction "TP_1") (pintype "bidirectional"))
    )
    (net (code "130") (name "VPP") (class "Default")
      (node (ref "U7") (pin "2") (pinfunction "VPP_2") (pintype "power_in"))
    )
    (net (code "131") (name "VUSB") (class "Default")
      (node (ref "D1") (pin "5") (pinfunction "5_5") (pintype "bidirectional"))
      (node (ref "F2") (pin "P$1") (pinfunction "1_P$1") (pintype "bidirectional"))
      (node (ref "USB1") (pin "VBUS1") (pinfunction "VBUS_VBUS1") (pintype "bidirectional"))
      (node (ref "USB1") (pin "VBUS2") (pinfunction "VBUS_VBUS2") (pintype "bidirectional"))
    )
    (net (code "132") (name "VUSB-MCU") (class "Default")
      (node (ref "J18") (pin "16") (pinfunction "NC_16") (pintype "power_in"))
      (node (ref "JP19") (pin "2") (pinfunction "2_2") (pintype "passive"))
      (node (ref "U1") (pin "1") (pinfunction "VOUT_1") (pintype "power_in"))
    )
    (net (code "133") (name "unconnected-(D1-Pad3)") (class "Default")
      (node (ref "D1") (pin "3") (pinfunction "3_3") (pintype "bidirectional"))
    )
    (net (code "134") (name "unconnected-(D1-Pad6)") (class "Default")
      (node (ref "D1") (pin "6") (pinfunction "6_6") (pintype "bidirectional"))
    )
    (net (code "135") (name "unconnected-(D23-Pad3)") (class "Default")
      (node (ref "D23") (pin "3") (pinfunction "3_3") (pintype "bidirectional"))
    )
    (net (code "136") (name "unconnected-(D23-Pad6)") (class "Default")
      (node (ref "D23") (pin "6") (pinfunction "6_6") (pintype "bidirectional"))
    )
    (net (code "137") (name "unconnected-(J3-Pad30)") (class "Default")
      (node (ref "J3") (pin "30") (pinfunction "30_30") (pintype "passive"))
    )
    (net (code "138") (name "unconnected-(J3-Pad32)") (class "Default")
      (node (ref "J3") (pin "32") (pinfunction "32_32") (pintype "passive"))
    )
    (net (code "139") (name "unconnected-(J11-5-PadNC1)") (class "Default")
      (node (ref "J11") (pin "NC1") (pinfunction "5_NC1") (pintype "bidirectional"))
    )
    (net (code "140") (name "unconnected-(J11-6-PadNC2)") (class "Default")
      (node (ref "J11") (pin "NC2") (pinfunction "6_NC2") (pintype "bidirectional"))
    )
    (net (code "141") (name "unconnected-(J13-VPP-PadC6)") (class "Default")
      (node (ref "J13") (pin "C6") (pinfunction "VPP_C6") (pintype "passive"))
    )
    (net (code "142") (name "unconnected-(JTAG-Pad7)") (class "Default")
      (node (ref "JTAG") (pin "7") (pinfunction "7_7") (pintype "bidirectional"))
    )
    (net (code "143") (name "unconnected-(JTAG-Pad8)") (class "Default")
      (node (ref "JTAG") (pin "8") (pinfunction "8_8") (pintype "bidirectional"))
    )
    (net (code "144") (name "unconnected-(U1-FLG-Pad3)") (class "Default")
      (node (ref "U1") (pin "3") (pinfunction "FLG_3") (pintype "bidirectional"))
    )
    (net (code "145") (name "unconnected-(U7-NA1-Pad4)") (class "Default")
      (node (ref "U7") (pin "4") (pinfunction "NA1_4") (pintype "bidirectional"))
    )
    (net (code "146") (name "unconnected-(U7-NA2-Pad5)") (class "Default")
      (node (ref "U7") (pin "5") (pinfunction "NA2_5") (pintype "bidirectional"))
    )
    (net (code "147") (name "unconnected-(X1-Pad1)") (class "Default")
      (node (ref "X1") (pin "1") (pinfunction "1_1") (pintype "passive"))
    )
    (net (code "148") (name "unconnected-(X2-Pad1)") (class "Default")
      (node (ref "X2") (pin "1") (pinfunction "1_1") (pintype "passive"))
    )
    (net (code "149") (name "unconnected-(X3-Pad1)") (class "Default")
      (node (ref "X3") (pin "1") (pinfunction "1_1") (pintype "passive"))
    )
    (net (code "150") (name "~{MODE}") (class "Default")
      (node (ref "J18") (pin "32") (pinfunction "~{MODE}_32") (pintype "bidirectional"))
      (node (ref "J3") (pin "18") (pinfunction "18_18") (pintype "passive"))
      (node (ref "MODE") (pin "3") (pinfunction "3_3") (pintype "passive"))
      (node (ref "MODE") (pin "4") (pinfunction "4_4") (pintype "passive"))
      (node (ref "R12") (pin "1") (pinfunction "1_1") (pintype "passive"))
    )
    (net (code "151") (name "~{RESET}") (class "Default")
      (node (ref "C1") (pin "1") (pinfunction "1_1") (pintype "passive"))
      (node (ref "J18") (pin "!RESET") (pinfunction "~{RESET}_!RESET") (pintype "power_in"))
      (node (ref "J18") (pin "34") (pinfunction "~{RESET}_34") (pintype "bidirectional"))
      (node (ref "J3") (pin "20") (pinfunction "20_20") (pintype "passive"))
      (node (ref "J6") (pin "23") (pinfunction "~{RST}_23") (pintype "passive"))
      (node (ref "J6") (pin "@23") (pinfunction "~{RST}_@23") (pintype "passive"))
      (node (ref "J6") (pin "P$23") (pinfunction "~{RST}_P$23") (pintype "passive"))
      (node (ref "JP5") (pin "1") (pinfunction "1_1") (pintype "passive"))
      (node (ref "JTAG") (pin "10") (pinfunction "10_10") (pintype "bidirectional"))
      (node (ref "R4") (pin "1") (pinfunction "1_1") (pintype "passive"))
      (node (ref "RESET") (pin "3") (pinfunction "3_3") (pintype "passive"))
      (node (ref "RESET") (pin "4") (pinfunction "4_4") (pintype "passive"))
    )
  )
)
